# main_v2.net
KiCad netlist of a schematic drawn in EAGLE
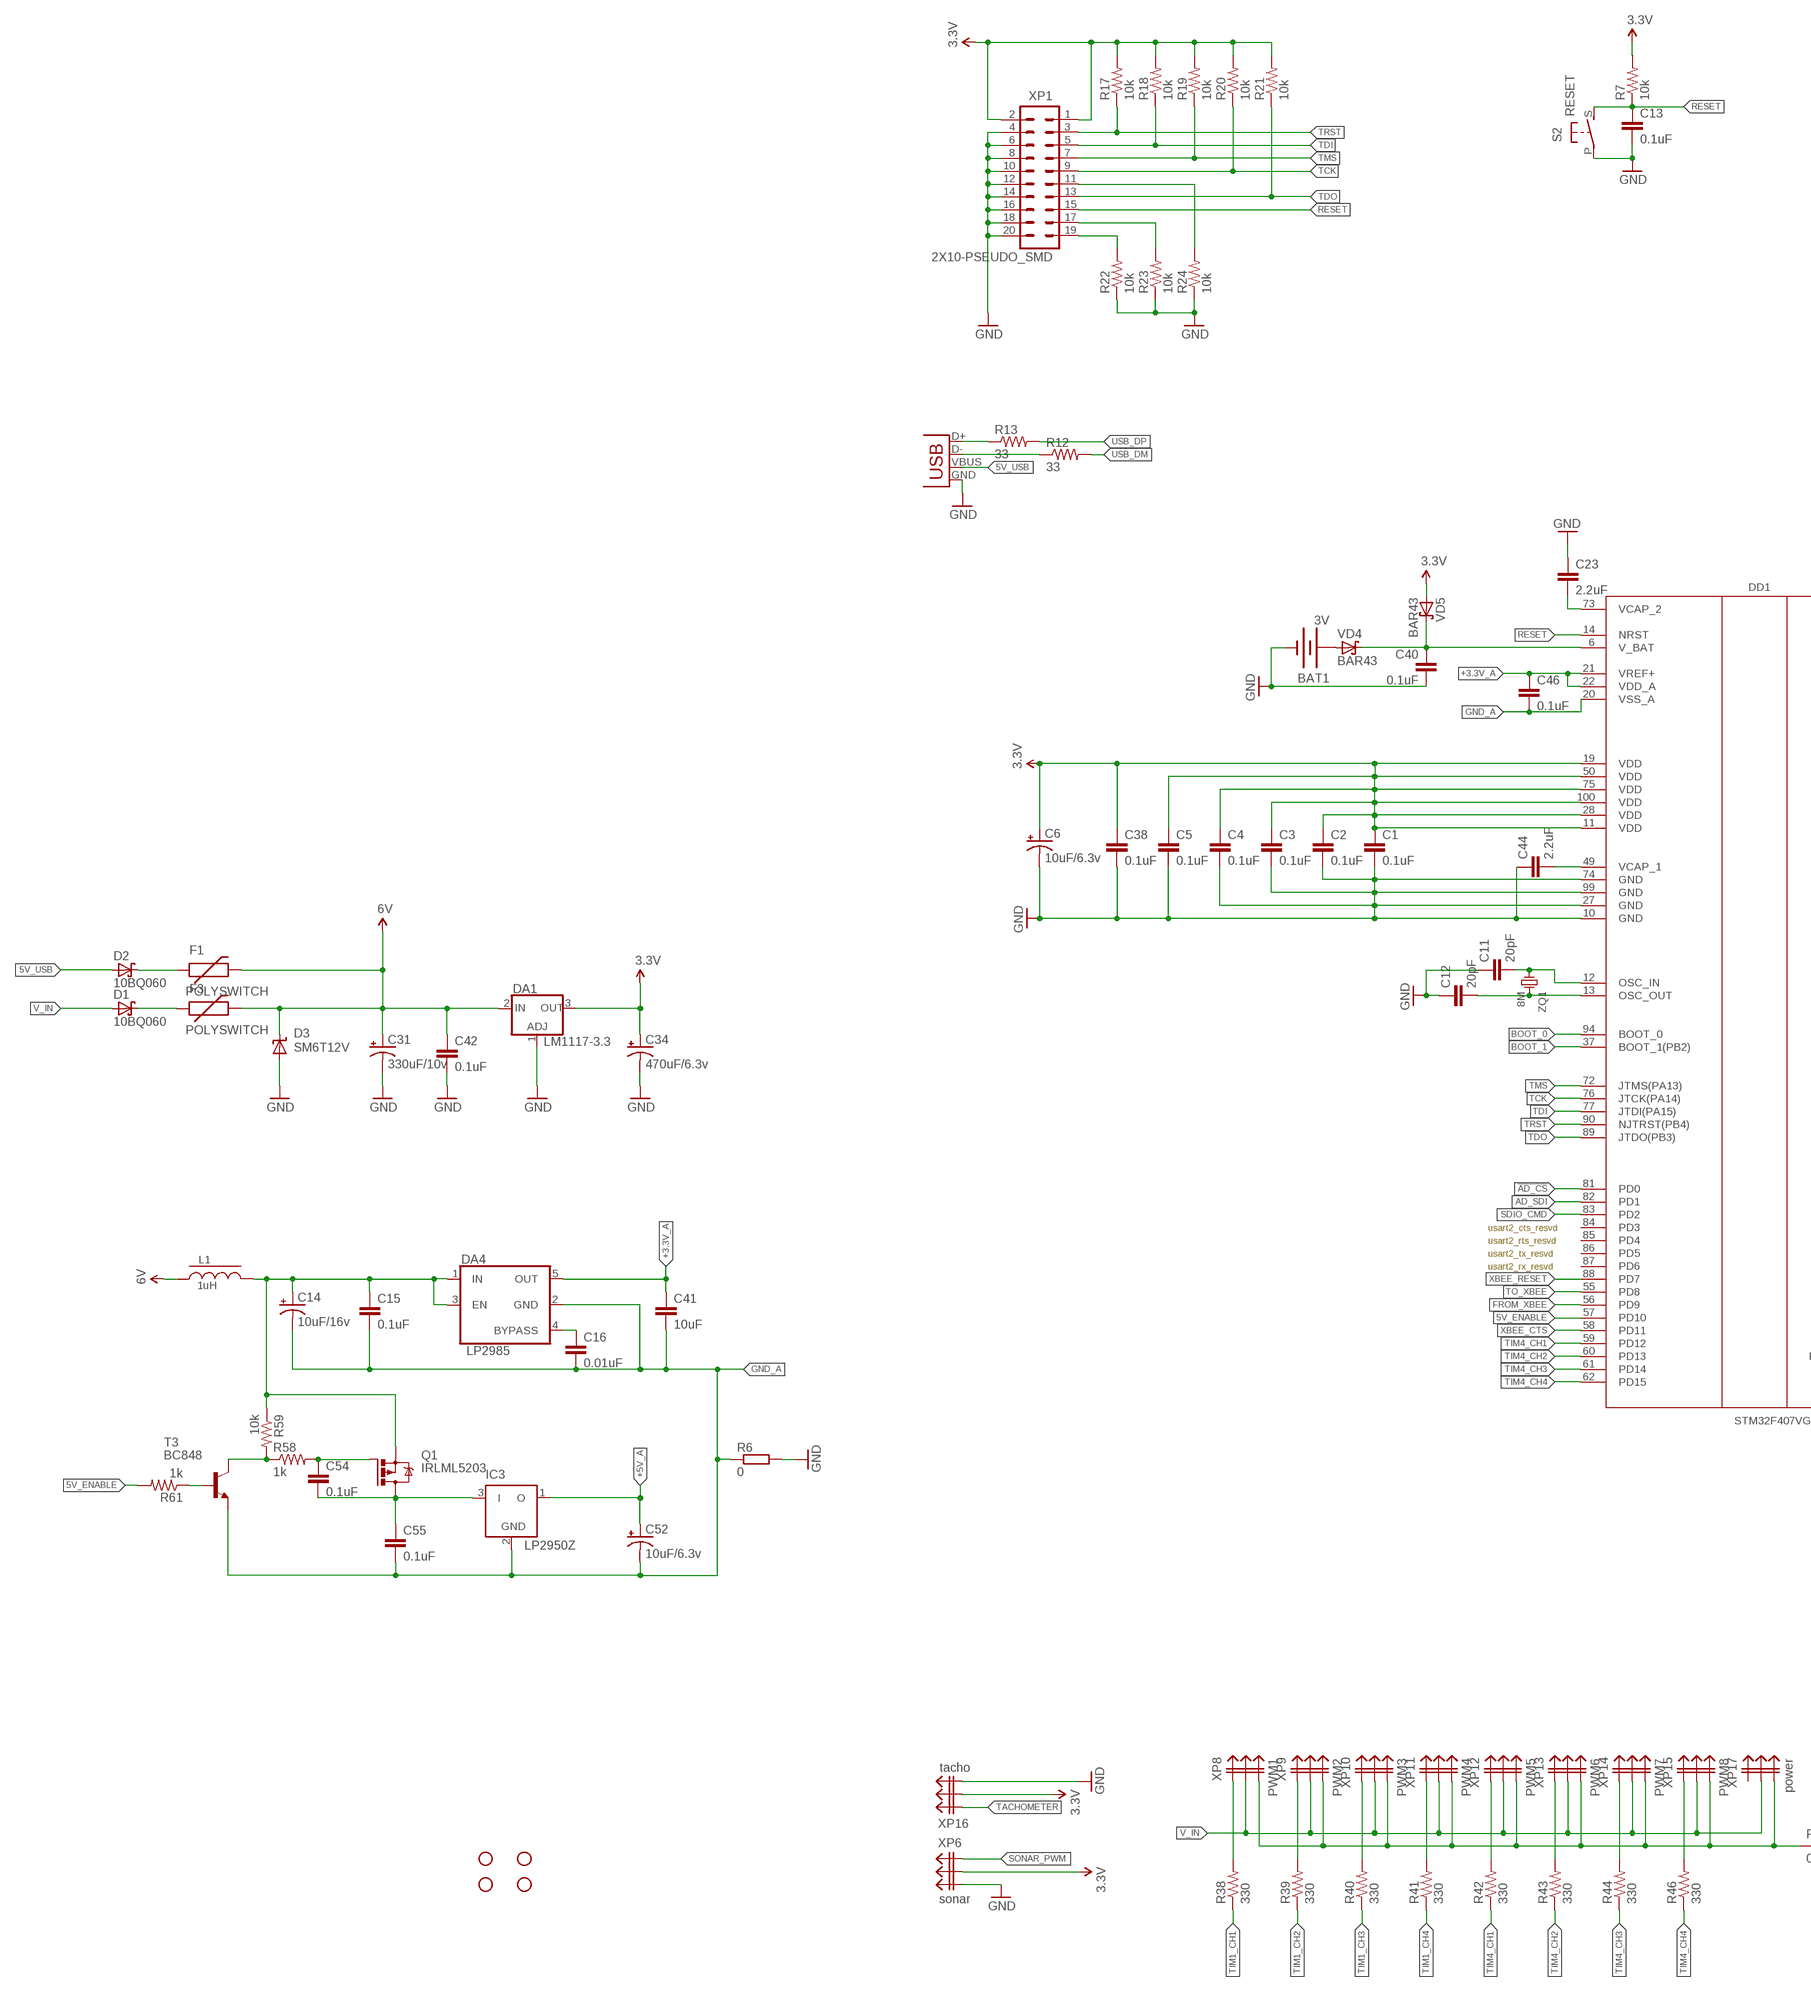
[diagram p0: schematic, sheet 1, part 1 of 3]
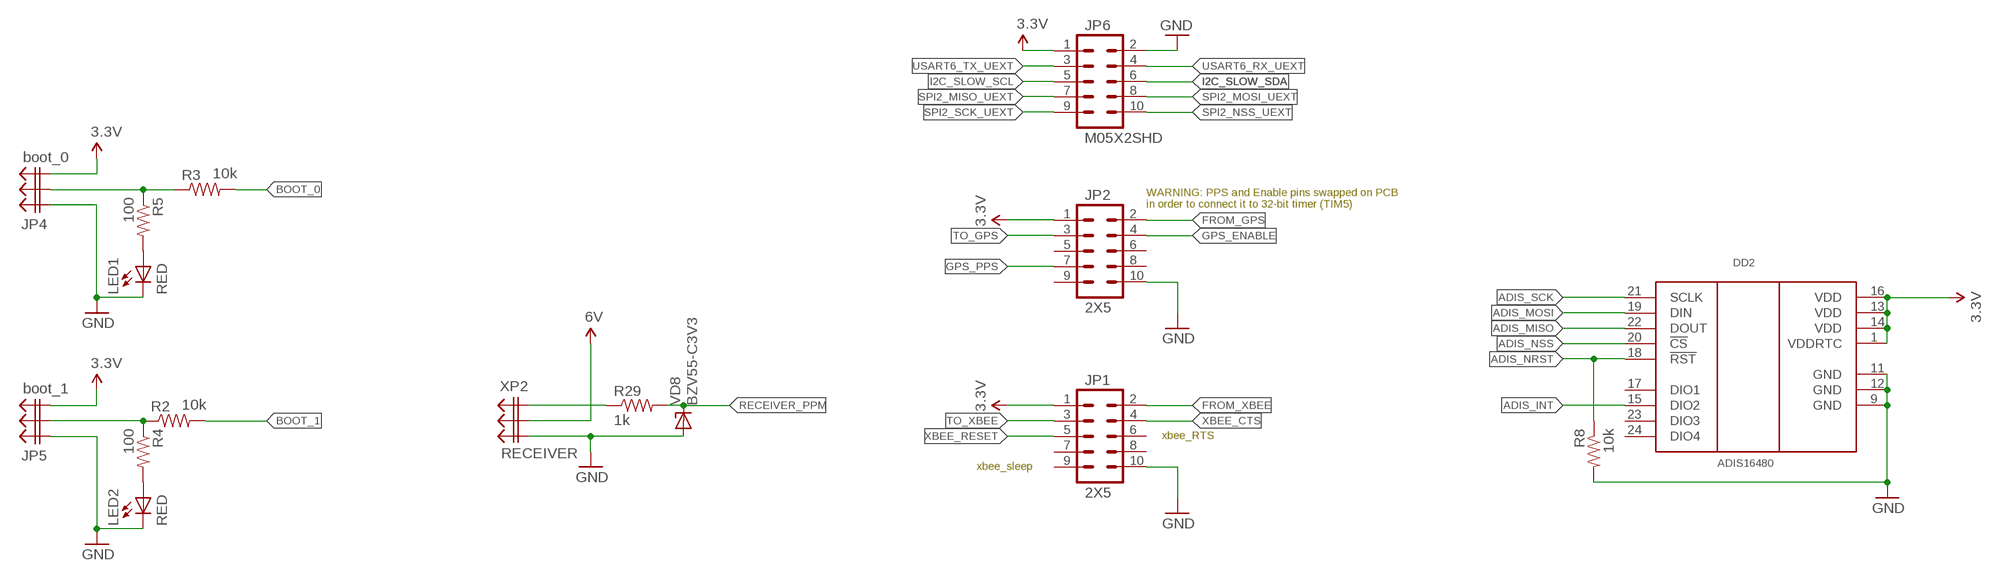
[diagram p1: schematic, sheet 1, part 2 of 3]
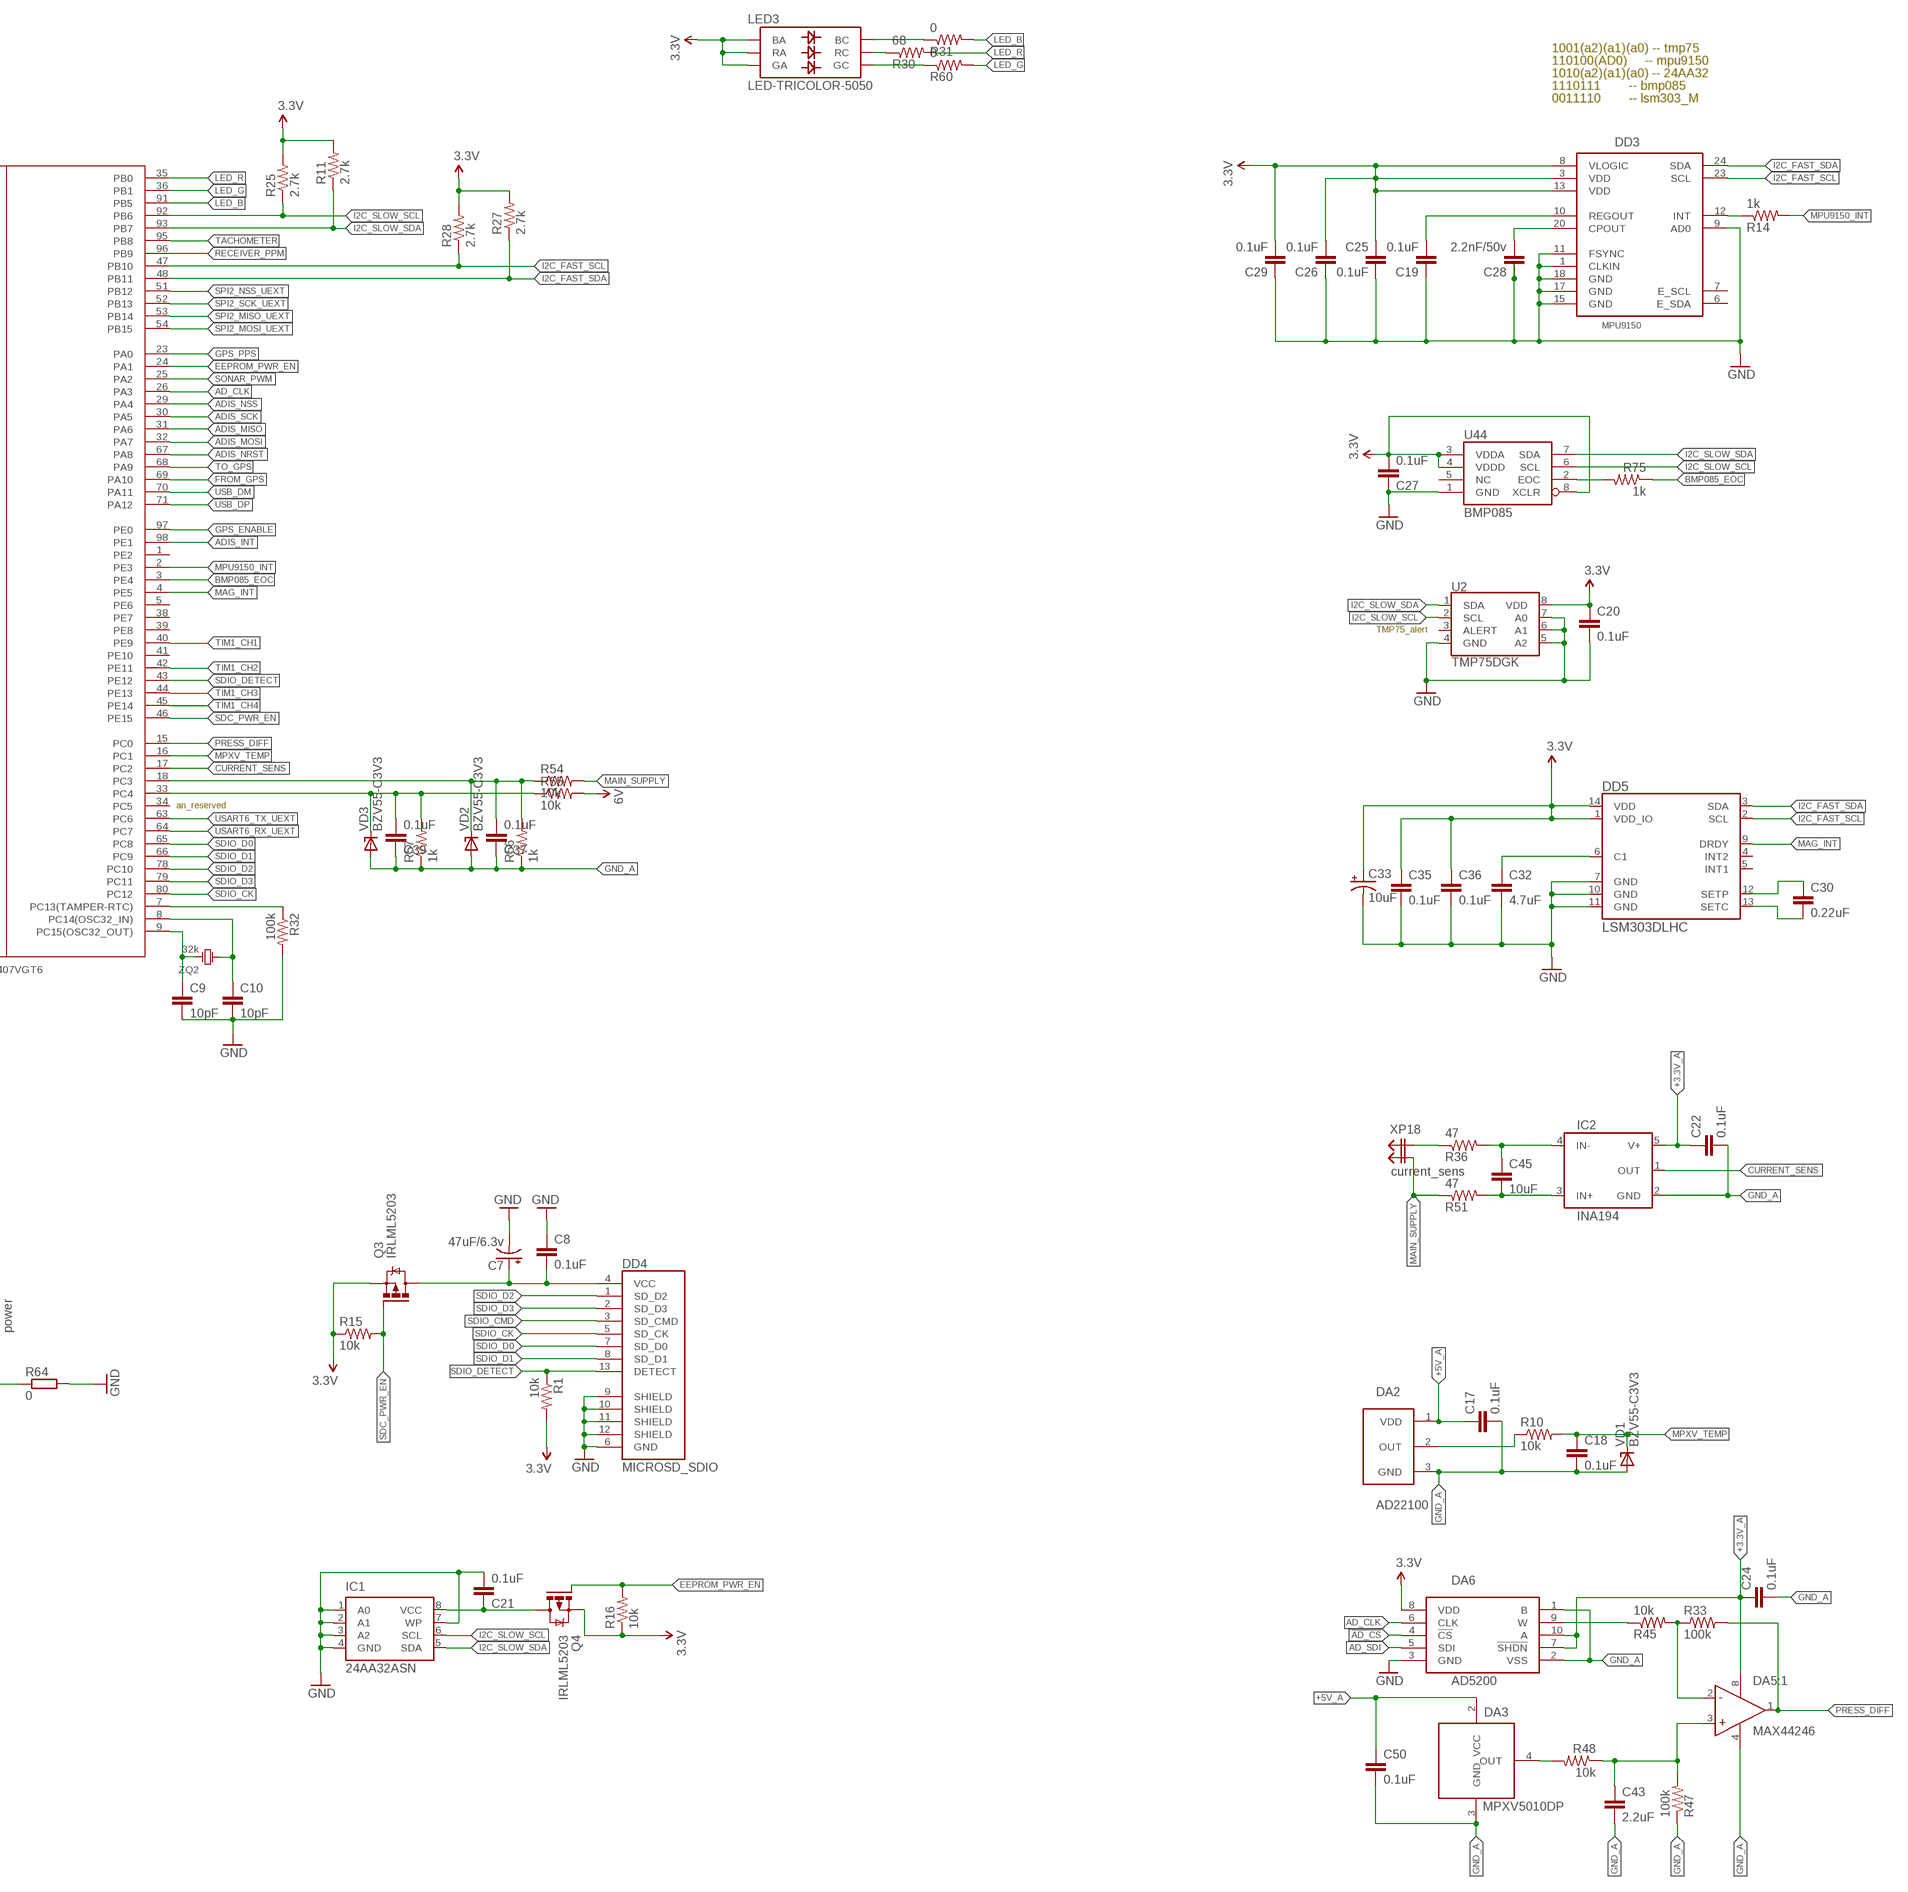
[diagram p2: schematic, sheet 1, part 3 of 3]

(export (version "E")
  (design (tool "Eeschema 10.0.6"))
  (components
    (comp (ref "BAT1")
      (value "3V")
      (footprint "eagle-import:BATTCOM_20MM_PTH")
      (libsource (lib "eagle-import") (part "BATTERY20PTH"))
    )
    (comp (ref "C1")
      (value "0.1uF")
      (footprint "eagle-import:0805")
      (libsource (lib "eagle-import") (part "CAP0805"))
    )
    (comp (ref "C2")
      (value "0.1uF")
      (footprint "eagle-import:0805")
      (libsource (lib "eagle-import") (part "CAP0805"))
    )
    (comp (ref "C3")
      (value "0.1uF")
      (footprint "eagle-import:0805")
      (libsource (lib "eagle-import") (part "CAP0805"))
    )
    (comp (ref "C4")
      (value "0.1uF")
      (footprint "eagle-import:0805")
      (libsource (lib "eagle-import") (part "CAP0805"))
    )
    (comp (ref "C5")
      (value "0.1uF")
      (footprint "eagle-import:0805")
      (libsource (lib "eagle-import") (part "CAP0805"))
    )
    (comp (ref "C6")
      (value "10uF/6.3v")
      (footprint "eagle-import:EIA3216-KIT")
      (libsource (lib "eagle-import") (part "CAP_POL1206-KIT"))
    )
    (comp (ref "C7")
      (value "47uF/6.3v")
      (footprint "eagle-import:EIA3216-KIT")
      (libsource (lib "eagle-import") (part "CAP_POL1206-KIT"))
    )
    (comp (ref "C8")
      (value "0.1uF")
      (footprint "eagle-import:0805")
      (libsource (lib "eagle-import") (part "CAP0805"))
    )
    (comp (ref "C9")
      (value "10pF")
      (footprint "eagle-import:0805")
      (libsource (lib "eagle-import") (part "CAP0805"))
    )
    (comp (ref "C10")
      (value "10pF")
      (footprint "eagle-import:0805")
      (libsource (lib "eagle-import") (part "CAP0805"))
    )
    (comp (ref "C11")
      (value "20pF")
      (footprint "eagle-import:0805")
      (libsource (lib "eagle-import") (part "CAP0805"))
    )
    (comp (ref "C12")
      (value "20pF")
      (footprint "eagle-import:0805")
      (libsource (lib "eagle-import") (part "CAP0805"))
    )
    (comp (ref "C13")
      (value "0.1uF")
      (footprint "eagle-import:0805")
      (libsource (lib "eagle-import") (part "CAP0805"))
    )
    (comp (ref "C14")
      (value "10uF/16v")
      (footprint "eagle-import:EIA3216-KIT")
      (libsource (lib "eagle-import") (part "CAP_POL1206-KIT"))
    )
    (comp (ref "C15")
      (value "0.1uF")
      (footprint "eagle-import:0805")
      (libsource (lib "eagle-import") (part "CAP0805"))
    )
    (comp (ref "C16")
      (value "0.01uF")
      (footprint "eagle-import:0805")
      (libsource (lib "eagle-import") (part "CAP0805"))
    )
    (comp (ref "C17")
      (value "0.1uF")
      (footprint "eagle-import:0805")
      (libsource (lib "eagle-import") (part "CAP0805"))
    )
    (comp (ref "C18")
      (value "0.1uF")
      (footprint "eagle-import:0805")
      (libsource (lib "eagle-import") (part "CAP0805"))
    )
    (comp (ref "C19")
      (value "0.1uF")
      (footprint "eagle-import:0805")
      (libsource (lib "eagle-import") (part "CAP0805"))
    )
    (comp (ref "C20")
      (value "0.1uF")
      (footprint "eagle-import:0805")
      (libsource (lib "eagle-import") (part "CAP0805"))
    )
    (comp (ref "C21")
      (value "0.1uF")
      (footprint "eagle-import:0805")
      (libsource (lib "eagle-import") (part "CAP0805"))
    )
    (comp (ref "C22")
      (value "0.1uF")
      (footprint "eagle-import:0805")
      (libsource (lib "eagle-import") (part "CAP0805"))
    )
    (comp (ref "C23")
      (value "2.2uF")
      (footprint "eagle-import:0805")
      (libsource (lib "eagle-import") (part "CAP0805"))
    )
    (comp (ref "C24")
      (value "0.1uF")
      (footprint "eagle-import:0805")
      (libsource (lib "eagle-import") (part "CAP0805"))
    )
    (comp (ref "C25")
      (value "0.1uF")
      (footprint "eagle-import:0805")
      (libsource (lib "eagle-import") (part "CAP0805"))
    )
    (comp (ref "C26")
      (value "0.1uF")
      (footprint "eagle-import:0805")
      (libsource (lib "eagle-import") (part "CAP0805"))
    )
    (comp (ref "C27")
      (value "0.1uF")
      (footprint "eagle-import:0805")
      (libsource (lib "eagle-import") (part "CAP0805"))
    )
    (comp (ref "C28")
      (value "2.2nF/50v")
      (footprint "eagle-import:0805")
      (libsource (lib "eagle-import") (part "CAP0805"))
    )
    (comp (ref "C29")
      (value "0.1uF")
      (footprint "eagle-import:0805")
      (libsource (lib "eagle-import") (part "CAP0805"))
    )
    (comp (ref "C30")
      (value "0.22uF")
      (footprint "eagle-import:0805")
      (libsource (lib "eagle-import") (part "CAP0805"))
    )
    (comp (ref "C31")
      (value "330uF/10v")
      (footprint "eagle-import:EIA7343")
      (libsource (lib "eagle-import") (part "barthess_CAP_POL7343"))
    )
    (comp (ref "C32")
      (value "4.7uF")
      (footprint "eagle-import:0805")
      (libsource (lib "eagle-import") (part "CAP0805"))
    )
    (comp (ref "C33")
      (value "10uF")
      (footprint "eagle-import:EIA3216-KIT")
      (libsource (lib "eagle-import") (part "CAP_POL1206-KIT"))
    )
    (comp (ref "C34")
      (value "470uF/6.3v")
      (footprint "eagle-import:EIA7343")
      (libsource (lib "eagle-import") (part "barthess_CAP_POL7343"))
    )
    (comp (ref "C35")
      (value "0.1uF")
      (footprint "eagle-import:0805")
      (libsource (lib "eagle-import") (part "CAP0805"))
    )
    (comp (ref "C36")
      (value "0.1uF")
      (footprint "eagle-import:0805")
      (libsource (lib "eagle-import") (part "CAP0805"))
    )
    (comp (ref "C37")
      (value "0.1uF")
      (footprint "eagle-import:0805")
      (libsource (lib "eagle-import") (part "CAP0805"))
    )
    (comp (ref "C38")
      (value "0.1uF")
      (footprint "eagle-import:0805")
      (libsource (lib "eagle-import") (part "CAP0805"))
    )
    (comp (ref "C39")
      (value "0.1uF")
      (footprint "eagle-import:0805")
      (libsource (lib "eagle-import") (part "CAP0805"))
    )
    (comp (ref "C40")
      (value "0.1uF")
      (footprint "eagle-import:0805")
      (libsource (lib "eagle-import") (part "CAP0805"))
    )
    (comp (ref "C41")
      (value "10uF")
      (footprint "eagle-import:1206")
      (libsource (lib "eagle-import") (part "CAP1206"))
    )
    (comp (ref "C42")
      (value "0.1uF")
      (footprint "eagle-import:0805")
      (libsource (lib "eagle-import") (part "CAP0805"))
    )
    (comp (ref "C43")
      (value "2.2uF")
      (footprint "eagle-import:0805")
      (libsource (lib "eagle-import") (part "CAP0805"))
    )
    (comp (ref "C44")
      (value "2.2uF")
      (footprint "eagle-import:0805")
      (libsource (lib "eagle-import") (part "CAP0805"))
    )
    (comp (ref "C45")
      (value "10uF")
      (footprint "eagle-import:1206")
      (libsource (lib "eagle-import") (part "CAP1206"))
    )
    (comp (ref "C46")
      (value "0.1uF")
      (footprint "eagle-import:0805")
      (libsource (lib "eagle-import") (part "CAP0805"))
    )
    (comp (ref "C50")
      (value "0.1uF")
      (footprint "eagle-import:0805")
      (libsource (lib "eagle-import") (part "CAP0805"))
    )
    (comp (ref "C52")
      (value "10uF/6.3v")
      (footprint "eagle-import:EIA3216-KIT")
      (libsource (lib "eagle-import") (part "CAP_POL1206-KIT"))
    )
    (comp (ref "C54")
      (value "0.1uF")
      (footprint "eagle-import:0805")
      (libsource (lib "eagle-import") (part "CAP0805"))
    )
    (comp (ref "C55")
      (value "0.1uF")
      (footprint "eagle-import:0805")
      (libsource (lib "eagle-import") (part "CAP0805"))
    )
    (comp (ref "D1")
      (value "10BQ060")
      (footprint "eagle-import:SMB")
      (libsource (lib "eagle-import") (part "SCHOTTKY-DIODESMD"))
    )
    (comp (ref "D2")
      (value "10BQ060")
      (footprint "eagle-import:SMB")
      (libsource (lib "eagle-import") (part "SCHOTTKY-DIODESMD"))
    )
    (comp (ref "D3")
      (value "SM6T12V")
      (footprint "eagle-import:SMBJ")
      (libsource (lib "eagle-import") (part "SUPPRESSOR-SMBJ"))
    )
    (comp (ref "DA1")
      (value "LM1117-3.3")
      (footprint "eagle-import:TO252")
      (libsource (lib "eagle-import") (part "LM1117DTX"))
    )
    (comp (ref "DA2")
      (value "AD22100")
      (footprint "eagle-import:TO92")
      (libsource (lib "eagle-import") (part "AD22100"))
    )
    (comp (ref "DA3")
      (value "MPXV5010DP")
      (footprint "eagle-import:482")
      (libsource (lib "eagle-import") (part "MPXV5010DP"))
    )
    (comp (ref "DA4")
      (value "LP2985")
      (footprint "eagle-import:SOT23-5")
      (libsource (lib "eagle-import") (part "LP2985"))
    )
    (comp (ref "DA5")
      (value "MAX44246")
      (footprint "eagle-import:MSOP8")
      (libsource (lib "eagle-import") (part "MAX44246"))
    )
    (comp (ref "DA6")
      (value "AD5200")
      (footprint "eagle-import:MSOP10")
      (libsource (lib "eagle-import") (part "AD5200"))
    )
    (comp (ref "DD1")
      (value "STM32F407VGT6")
      (footprint "eagle-import:TQFP100")
      (libsource (lib "eagle-import") (part "STM32F407VGT6"))
    )
    (comp (ref "DD2")
      (value "ADIS16480")
      (footprint "eagle-import:ADIS16480")
      (libsource (lib "eagle-import") (part "ADIS16480"))
    )
    (comp (ref "DD3")
      (value "MPU9150")
      (footprint "eagle-import:QFN-24-NP")
      (libsource (lib "eagle-import") (part "MPU-9150QFN-24-NP"))
    )
    (comp (ref "DD4")
      (value "MICROSD_SDIO")
      (footprint "eagle-import:MICROSD")
      (libsource (lib "eagle-import") (part "MICROSD_SDIO"))
    )
    (comp (ref "DD5")
      (value "LSM303DLHC")
      (footprint "eagle-import:LGA14")
      (libsource (lib "eagle-import") (part "LSM303DLHC"))
    )
    (comp (ref "F1")
      (value "POLYSWITCH")
      (footprint "eagle-import:1812")
      (libsource (lib "eagle-import") (part "POLYSWITCH"))
    )
    (comp (ref "F3")
      (value "POLYSWITCH")
      (footprint "eagle-import:1812")
      (libsource (lib "eagle-import") (part "POLYSWITCH"))
    )
    (comp (ref "IC1")
      (value "24AA32ASN")
      (footprint "eagle-import:SO-08")
      (fields (field (name "MF") "MICROCHIP") (field (name "MPN") "24AA32A-I/SN"))
      (libsource (lib "eagle-import") (part "24SNAA32A"))
    )
    (comp (ref "IC2")
      (value "INA194")
      (footprint "eagle-import:SOT23-5")
      (fields (field (name "MF") "TEXAS INSTRUMENTS") (field (name "MPN") "INA168NA/250"))
      (libsource (lib "eagle-import") (part "INA194"))
    )
    (comp (ref "IC3")
      (value "LP2950Z")
      (footprint "eagle-import:TO92")
      (libsource (lib "eagle-import") (part "LP2950Z"))
    )
    (comp (ref "JP1")
      (value "2X5")
      (footprint "eagle-import:PLD_2X05_PSEUDOSMD")
      (libsource (lib "eagle-import") (part "2X5"))
    )
    (comp (ref "JP2")
      (value "2X5")
      (footprint "eagle-import:PLD_2X05_PSEUDOSMD")
      (libsource (lib "eagle-import") (part "2X5"))
    )
    (comp (ref "JP3")
      (value "STAND-OFF")
      (footprint "eagle-import:STAND-OFF")
      (libsource (lib "eagle-import") (part "STAND-OFF"))
    )
    (comp (ref "JP4")
      (value "boot_0")
      (footprint "eagle-import:PLD_1X03")
      (libsource (lib "eagle-import") (part "PLD_1X03"))
    )
    (comp (ref "JP5")
      (value "boot_1")
      (footprint "eagle-import:PLD_1X03")
      (libsource (lib "eagle-import") (part "PLD_1X03"))
    )
    (comp (ref "JP6")
      (value "M05X2SHD")
      (footprint "eagle-import:2X5-SHROUDED")
      (libsource (lib "eagle-import") (part "M05X2SHD"))
    )
    (comp (ref "JP7")
      (value "STAND-OFF")
      (footprint "eagle-import:STAND-OFF")
      (libsource (lib "eagle-import") (part "STAND-OFF"))
    )
    (comp (ref "JP8")
      (value "STAND-OFF")
      (footprint "eagle-import:STAND-OFF")
      (libsource (lib "eagle-import") (part "STAND-OFF"))
    )
    (comp (ref "JP9")
      (value "STAND-OFF")
      (footprint "eagle-import:STAND-OFF")
      (libsource (lib "eagle-import") (part "STAND-OFF"))
    )
    (comp (ref "L1")
      (value "1uH")
      (footprint "eagle-import:L0603")
      (libsource (lib "eagle-import") (part "EXC3BP"))
    )
    (comp (ref "LED1")
      (value "RED")
      (footprint "eagle-import:LED-0805")
      (libsource (lib "eagle-import") (part "LED0805"))
    )
    (comp (ref "LED2")
      (value "RED")
      (footprint "eagle-import:LED-0805")
      (libsource (lib "eagle-import") (part "LED0805"))
    )
    (comp (ref "LED3")
      (value "LED-TRICOLOR-5050")
      (footprint "eagle-import:LED-TRICOLOR-5050")
      (libsource (lib "eagle-import") (part "LED-TRICOLOR-5050"))
    )
    (comp (ref "Q1")
      (value "IRLML5203")
      (footprint "eagle-import:MICRO3")
      (libsource (lib "eagle-import") (part "IRLML5203"))
    )
    (comp (ref "Q3")
      (value "IRLML5203")
      (footprint "eagle-import:MICRO3")
      (libsource (lib "eagle-import") (part "IRLML5203"))
    )
    (comp (ref "Q4")
      (value "IRLML5203")
      (footprint "eagle-import:MICRO3")
      (libsource (lib "eagle-import") (part "IRLML5203"))
    )
    (comp (ref "R1")
      (value "10k")
      (footprint "eagle-import:0805")
      (libsource (lib "eagle-import") (part "RESISTOR0805-RES"))
    )
    (comp (ref "R2")
      (value "10k")
      (footprint "eagle-import:0805")
      (libsource (lib "eagle-import") (part "RESISTOR0805-RES"))
    )
    (comp (ref "R3")
      (value "10k")
      (footprint "eagle-import:0805")
      (libsource (lib "eagle-import") (part "RESISTOR0805-RES"))
    )
    (comp (ref "R4")
      (value "100")
      (footprint "eagle-import:0805")
      (libsource (lib "eagle-import") (part "RESISTOR0805-RES"))
    )
    (comp (ref "R5")
      (value "100")
      (footprint "eagle-import:0805")
      (libsource (lib "eagle-import") (part "RESISTOR0805-RES"))
    )
    (comp (ref "R6")
      (value "0")
      (footprint "eagle-import:1206")
      (libsource (lib "eagle-import") (part "barthess_RESISTOR1206"))
    )
    (comp (ref "R7")
      (value "10k")
      (footprint "eagle-import:0805")
      (libsource (lib "eagle-import") (part "RESISTOR0805-RES"))
    )
    (comp (ref "R8")
      (value "10k")
      (footprint "eagle-import:0805")
      (libsource (lib "eagle-import") (part "RESISTOR0805-RES"))
    )
    (comp (ref "R10")
      (value "10k")
      (footprint "eagle-import:0805")
      (libsource (lib "eagle-import") (part "RESISTOR0805-RES"))
    )
    (comp (ref "R11")
      (value "2.7k")
      (footprint "eagle-import:0805")
      (libsource (lib "eagle-import") (part "RESISTOR0805-RES"))
    )
    (comp (ref "R12")
      (value "33")
      (footprint "eagle-import:0805")
      (libsource (lib "eagle-import") (part "RESISTOR0805-RES"))
    )
    (comp (ref "R13")
      (value "33")
      (footprint "eagle-import:0805")
      (libsource (lib "eagle-import") (part "RESISTOR0805-RES"))
    )
    (comp (ref "R14")
      (value "1k")
      (footprint "eagle-import:0805")
      (libsource (lib "eagle-import") (part "RESISTOR0805-RES"))
    )
    (comp (ref "R15")
      (value "10k")
      (footprint "eagle-import:0805")
      (libsource (lib "eagle-import") (part "RESISTOR0805-RES"))
    )
    (comp (ref "R16")
      (value "10k")
      (footprint "eagle-import:0805")
      (libsource (lib "eagle-import") (part "RESISTOR0805-RES"))
    )
    (comp (ref "R17")
      (value "10k")
      (footprint "eagle-import:0805")
      (libsource (lib "eagle-import") (part "RESISTOR0805-RES"))
    )
    (comp (ref "R18")
      (value "10k")
      (footprint "eagle-import:0805")
      (libsource (lib "eagle-import") (part "RESISTOR0805-RES"))
    )
    (comp (ref "R19")
      (value "10k")
      (footprint "eagle-import:0805")
      (libsource (lib "eagle-import") (part "RESISTOR0805-RES"))
    )
    (comp (ref "R20")
      (value "10k")
      (footprint "eagle-import:0805")
      (libsource (lib "eagle-import") (part "RESISTOR0805-RES"))
    )
    (comp (ref "R21")
      (value "10k")
      (footprint "eagle-import:0805")
      (libsource (lib "eagle-import") (part "RESISTOR0805-RES"))
    )
    (comp (ref "R22")
      (value "10k")
      (footprint "eagle-import:0805")
      (libsource (lib "eagle-import") (part "RESISTOR0805-RES"))
    )
    (comp (ref "R23")
      (value "10k")
      (footprint "eagle-import:0805")
      (libsource (lib "eagle-import") (part "RESISTOR0805-RES"))
    )
    (comp (ref "R24")
      (value "10k")
      (footprint "eagle-import:0805")
      (libsource (lib "eagle-import") (part "RESISTOR0805-RES"))
    )
    (comp (ref "R25")
      (value "2.7k")
      (footprint "eagle-import:0805")
      (libsource (lib "eagle-import") (part "RESISTOR0805-RES"))
    )
    (comp (ref "R27")
      (value "2.7k")
      (footprint "eagle-import:0805")
      (libsource (lib "eagle-import") (part "RESISTOR0805-RES"))
    )
    (comp (ref "R28")
      (value "2.7k")
      (footprint "eagle-import:0805")
      (libsource (lib "eagle-import") (part "RESISTOR0805-RES"))
    )
    (comp (ref "R29")
      (value "1k")
      (footprint "eagle-import:0805")
      (libsource (lib "eagle-import") (part "RESISTOR0805-RES"))
    )
    (comp (ref "R30")
      (value "68")
      (footprint "eagle-import:0805")
      (libsource (lib "eagle-import") (part "RESISTOR0805-RES"))
    )
    (comp (ref "R31")
      (value "0")
      (footprint "eagle-import:0805")
      (libsource (lib "eagle-import") (part "RESISTOR0805-RES"))
    )
    (comp (ref "R32")
      (value "100k")
      (footprint "eagle-import:0805")
      (libsource (lib "eagle-import") (part "RESISTOR0805-RES"))
    )
    (comp (ref "R33")
      (value "100k")
      (footprint "eagle-import:0805")
      (libsource (lib "eagle-import") (part "RESISTOR0805-RES"))
    )
    (comp (ref "R36")
      (value "47")
      (footprint "eagle-import:0805")
      (libsource (lib "eagle-import") (part "RESISTOR0805-RES"))
    )
    (comp (ref "R38")
      (value "330")
      (footprint "eagle-import:0805")
      (libsource (lib "eagle-import") (part "RESISTOR0805-RES"))
    )
    (comp (ref "R39")
      (value "330")
      (footprint "eagle-import:0805")
      (libsource (lib "eagle-import") (part "RESISTOR0805-RES"))
    )
    (comp (ref "R40")
      (value "330")
      (footprint "eagle-import:0805")
      (libsource (lib "eagle-import") (part "RESISTOR0805-RES"))
    )
    (comp (ref "R41")
      (value "330")
      (footprint "eagle-import:0805")
      (libsource (lib "eagle-import") (part "RESISTOR0805-RES"))
    )
    (comp (ref "R42")
      (value "330")
      (footprint "eagle-import:0805")
      (libsource (lib "eagle-import") (part "RESISTOR0805-RES"))
    )
    (comp (ref "R43")
      (value "330")
      (footprint "eagle-import:0805")
      (libsource (lib "eagle-import") (part "RESISTOR0805-RES"))
    )
    (comp (ref "R44")
      (value "330")
      (footprint "eagle-import:0805")
      (libsource (lib "eagle-import") (part "RESISTOR0805-RES"))
    )
    (comp (ref "R45")
      (value "10k")
      (footprint "eagle-import:0805")
      (libsource (lib "eagle-import") (part "RESISTOR0805-RES"))
    )
    (comp (ref "R46")
      (value "330")
      (footprint "eagle-import:0805")
      (libsource (lib "eagle-import") (part "RESISTOR0805-RES"))
    )
    (comp (ref "R47")
      (value "100k")
      (footprint "eagle-import:0805")
      (libsource (lib "eagle-import") (part "RESISTOR0805-RES"))
    )
    (comp (ref "R48")
      (value "10k")
      (footprint "eagle-import:0805")
      (libsource (lib "eagle-import") (part "RESISTOR0805-RES"))
    )
    (comp (ref "R51")
      (value "47")
      (footprint "eagle-import:0805")
      (libsource (lib "eagle-import") (part "RESISTOR0805-RES"))
    )
    (comp (ref "R54")
      (value "10k")
      (footprint "eagle-import:0805")
      (libsource (lib "eagle-import") (part "RESISTOR0805-RES"))
    )
    (comp (ref "R55")
      (value "10k")
      (footprint "eagle-import:0805")
      (libsource (lib "eagle-import") (part "RESISTOR0805-RES"))
    )
    (comp (ref "R56")
      (value "1k")
      (footprint "eagle-import:0805")
      (libsource (lib "eagle-import") (part "RESISTOR0805-RES"))
    )
    (comp (ref "R57")
      (value "1k")
      (footprint "eagle-import:0805")
      (libsource (lib "eagle-import") (part "RESISTOR0805-RES"))
    )
    (comp (ref "R58")
      (value "1k")
      (footprint "eagle-import:0805")
      (libsource (lib "eagle-import") (part "RESISTOR0805-RES"))
    )
    (comp (ref "R59")
      (value "10k")
      (footprint "eagle-import:0805")
      (libsource (lib "eagle-import") (part "RESISTOR0805-RES"))
    )
    (comp (ref "R60")
      (value "0")
      (footprint "eagle-import:0805")
      (libsource (lib "eagle-import") (part "RESISTOR0805-RES"))
    )
    (comp (ref "R61")
      (value "1k")
      (footprint "eagle-import:0805")
      (libsource (lib "eagle-import") (part "RESISTOR0805-RES"))
    )
    (comp (ref "R64")
      (value "0")
      (footprint "eagle-import:1206")
      (libsource (lib "eagle-import") (part "barthess_RESISTOR1206"))
    )
    (comp (ref "R75")
      (value "1k")
      (footprint "eagle-import:0805")
      (libsource (lib "eagle-import") (part "RESISTOR0805-RES"))
    )
    (comp (ref "S2")
      (value "RESET")
      (footprint "eagle-import:BUTTON_6X3.5")
      (libsource (lib "eagle-import") (part "BUTTON_6X3.5"))
    )
    (comp (ref "T3")
      (value "BC848")
      (footprint "eagle-import:SOT23")
      (libsource (lib "eagle-import") (part "BC848"))
    )
    (comp (ref "U2")
      (value "TMP75DGK")
      (footprint "eagle-import:MSOP8")
      (libsource (lib "eagle-import") (part "TMP75DGK"))
    )
    (comp (ref "U44")
      (value "BMP085")
      (footprint "eagle-import:BMP085")
      (libsource (lib "eagle-import") (part "BMP085"))
    )
    (comp (ref "VD1")
      (value "BZV55-C3V3")
      (footprint "eagle-import:SOD80C")
      (fields (field (name "PARTNO") "?"))
      (libsource (lib "eagle-import") (part "BZV55-C3V3"))
    )
    (comp (ref "VD2")
      (value "BZV55-C3V3")
      (footprint "eagle-import:SOD80C")
      (fields (field (name "PARTNO") "?"))
      (libsource (lib "eagle-import") (part "BZV55-C3V3"))
    )
    (comp (ref "VD3")
      (value "BZV55-C3V3")
      (footprint "eagle-import:SOD80C")
      (fields (field (name "PARTNO") "?"))
      (libsource (lib "eagle-import") (part "BZV55-C3V3"))
    )
    (comp (ref "VD4")
      (value "BAR43")
      (footprint "eagle-import:SOT23-3")
      (libsource (lib "eagle-import") (part "BAR43"))
    )
    (comp (ref "VD5")
      (value "BAR43")
      (footprint "eagle-import:SOT23-3")
      (libsource (lib "eagle-import") (part "BAR43"))
    )
    (comp (ref "VD8")
      (value "BZV55-C3V3")
      (footprint "eagle-import:SOD80C")
      (fields (field (name "PARTNO") "?"))
      (libsource (lib "eagle-import") (part "BZV55-C3V3"))
    )
    (comp (ref "X1")
      (value "USB-SMD-NS")
      (footprint "eagle-import:USB-MINIB-NOSTOP")
      (libsource (lib "eagle-import") (part "USB-SMD-NS"))
    )
    (comp (ref "XP1")
      (value "2X10-PSEUDO_SMD")
      (footprint "eagle-import:PLD_2X10_PSEUDOSMD")
      (libsource (lib "eagle-import") (part "2X10-PSEUDO_SMD"))
    )
    (comp (ref "XP2")
      (value "RECEIVER")
      (footprint "eagle-import:PLD_1X03")
      (libsource (lib "eagle-import") (part "PLD_1X03"))
    )
    (comp (ref "XP6")
      (value "sonar")
      (footprint "eagle-import:PLD_1X03")
      (libsource (lib "eagle-import") (part "PLD_1X03"))
    )
    (comp (ref "XP8")
      (value "PWM1")
      (footprint "eagle-import:PLD_1X03")
      (libsource (lib "eagle-import") (part "PLD_1X03"))
    )
    (comp (ref "XP9")
      (value "PWM2")
      (footprint "eagle-import:PLD_1X03")
      (libsource (lib "eagle-import") (part "PLD_1X03"))
    )
    (comp (ref "XP10")
      (value "PWM3")
      (footprint "eagle-import:PLD_1X03")
      (libsource (lib "eagle-import") (part "PLD_1X03"))
    )
    (comp (ref "XP11")
      (value "PWM4")
      (footprint "eagle-import:PLD_1X03")
      (libsource (lib "eagle-import") (part "PLD_1X03"))
    )
    (comp (ref "XP12")
      (value "PWM5")
      (footprint "eagle-import:PLD_1X03")
      (libsource (lib "eagle-import") (part "PLD_1X03"))
    )
    (comp (ref "XP13")
      (value "PWM6")
      (footprint "eagle-import:PLD_1X03")
      (libsource (lib "eagle-import") (part "PLD_1X03"))
    )
    (comp (ref "XP14")
      (value "PWM7")
      (footprint "eagle-import:PLD_1X03")
      (libsource (lib "eagle-import") (part "PLD_1X03"))
    )
    (comp (ref "XP15")
      (value "PWM8")
      (footprint "eagle-import:PLD_1X03")
      (libsource (lib "eagle-import") (part "PLD_1X03"))
    )
    (comp (ref "XP16")
      (value "tacho")
      (footprint "eagle-import:PLD_1X03")
      (libsource (lib "eagle-import") (part "PLD_1X03"))
    )
    (comp (ref "XP17")
      (value "power")
      (footprint "eagle-import:PLD_1X03")
      (libsource (lib "eagle-import") (part "PLD_1X03"))
    )
    (comp (ref "XP18")
      (value "current_sens")
      (footprint "eagle-import:PLD_1X02")
      (libsource (lib "eagle-import") (part "1X2DIP"))
    )
    (comp (ref "ZQ1")
      (value "8M")
      (footprint "eagle-import:CRYSTAL-SMD-5X3")
      (libsource (lib "eagle-import") (part "CRYSTAL5X3"))
    )
    (comp (ref "ZQ2")
      (value "32k")
      (footprint "eagle-import:CRYSTAL-32KHZ-SMD-3.2X1.5")
      (libsource (lib "eagle-import") (part "CRYSTAL3.2X.1.5"))
    )
  )
  (nets
    (net (code "1") (name "+3.3V_A") (class "Default")
      (node (ref "C22") (pin "1") (pinfunction "1_1") (pintype "passive"))
      (node (ref "C24") (pin "1") (pinfunction "1_1") (pintype "passive"))
      (node (ref "C41") (pin "1") (pinfunction "1_1") (pintype "passive"))
      (node (ref "C46") (pin "1") (pinfunction "1_1") (pintype "passive"))
      (node (ref "DA4") (pin "5") (pinfunction "OUT_5") (pintype "power_in"))
      (node (ref "DA5") (pin "8") (pinfunction "+V_8") (pintype "power_in"))
      (node (ref "DA6") (pin "10") (pinfunction "A_10") (pintype "bidirectional"))
      (node (ref "DA6") (pin "7") (pinfunction "~{SHDN}_7") (pintype "bidirectional"))
      (node (ref "DD1") (pin "21") (pinfunction "VREF+_21") (pintype "power_in"))
      (node (ref "DD1") (pin "22") (pinfunction "VDD_A_22") (pintype "power_in"))
      (node (ref "IC2") (pin "5") (pinfunction "V+_5") (pintype "power_in"))
    )
    (net (code "2") (name "+5V_A") (class "Default")
      (node (ref "C17") (pin "1") (pinfunction "1_1") (pintype "passive"))
      (node (ref "C50") (pin "1") (pinfunction "1_1") (pintype "passive"))
      (node (ref "C52") (pin "A") (pinfunction "+_A") (pintype "passive"))
      (node (ref "DA2") (pin "1") (pinfunction "VDD_1") (pintype "power_in"))
      (node (ref "DA3") (pin "2") (pinfunction "VCC_2") (pintype "power_in"))
      (node (ref "IC3") (pin "1") (pinfunction "O_1") (pintype "input"))
    )
    (net (code "3") (name "/~{AD_CS}") (class "Default")
      (node (ref "DA6") (pin "4") (pinfunction "~{CS}_4") (pintype "bidirectional"))
      (node (ref "DD1") (pin "81") (pinfunction "PD0_81") (pintype "bidirectional"))
    )
    (net (code "4") (name "3.3V") (class "Default")
      (node (ref "C1") (pin "1") (pinfunction "1_1") (pintype "passive"))
      (node (ref "C2") (pin "1") (pinfunction "1_1") (pintype "passive"))
      (node (ref "C20") (pin "1") (pinfunction "1_1") (pintype "passive"))
      (node (ref "C25") (pin "1") (pinfunction "1_1") (pintype "passive"))
      (node (ref "C26") (pin "2") (pinfunction "2_2") (pintype "passive"))
      (node (ref "C27") (pin "2") (pinfunction "2_2") (pintype "passive"))
      (node (ref "C29") (pin "2") (pinfunction "2_2") (pintype "passive"))
      (node (ref "C3") (pin "1") (pinfunction "1_1") (pintype "passive"))
      (node (ref "C33") (pin "A") (pinfunction "+_A") (pintype "passive"))
      (node (ref "C34") (pin "A") (pinfunction "+_A") (pintype "passive"))
      (node (ref "C35") (pin "1") (pinfunction "1_1") (pintype "passive"))
      (node (ref "C36") (pin "1") (pinfunction "1_1") (pintype "passive"))
      (node (ref "C38") (pin "1") (pinfunction "1_1") (pintype "passive"))
      (node (ref "C4") (pin "1") (pinfunction "1_1") (pintype "passive"))
      (node (ref "C5") (pin "1") (pinfunction "1_1") (pintype "passive"))
      (node (ref "C6") (pin "A") (pinfunction "+_A") (pintype "passive"))
      (node (ref "DA1") (pin "3") (pinfunction "OUT_3") (pintype "power_in"))
      (node (ref "DA6") (pin "8") (pinfunction "VDD_8") (pintype "bidirectional"))
      (node (ref "DD1") (pin "100") (pinfunction "VDD_100") (pintype "power_in"))
      (node (ref "DD1") (pin "11") (pinfunction "VDD_11") (pintype "power_in"))
      (node (ref "DD1") (pin "19") (pinfunction "VDD_19") (pintype "power_in"))
      (node (ref "DD1") (pin "28") (pinfunction "VDD_28") (pintype "power_in"))
      (node (ref "DD1") (pin "50") (pinfunction "VDD_50") (pintype "power_in"))
      (node (ref "DD1") (pin "75") (pinfunction "VDD_75") (pintype "power_in"))
      (node (ref "DD2") (pin "1") (pinfunction "VDDRTC_1") (pintype "power_in"))
      (node (ref "DD2") (pin "13") (pinfunction "VDD_13") (pintype "power_in"))
      (node (ref "DD2") (pin "14") (pinfunction "VDD_14") (pintype "power_in"))
      (node (ref "DD2") (pin "16") (pinfunction "VDD_16") (pintype "power_in"))
      (node (ref "DD3") (pin "13") (pinfunction "VDD_13") (pintype "bidirectional"))
      (node (ref "DD3") (pin "3") (pinfunction "VDD_3") (pintype "bidirectional"))
      (node (ref "DD3") (pin "8") (pinfunction "VLOGIC_8") (pintype "bidirectional"))
      (node (ref "DD5") (pin "1") (pinfunction "VDD_IO_1") (pintype "bidirectional"))
      (node (ref "DD5") (pin "14") (pinfunction "VDD_14") (pintype "bidirectional"))
      (node (ref "JP1") (pin "1") (pinfunction "1_1") (pintype "passive"))
      (node (ref "JP2") (pin "1") (pinfunction "1_1") (pintype "passive"))
      (node (ref "JP4") (pin "3") (pinfunction "3_3") (pintype "passive"))
      (node (ref "JP5") (pin "3") (pinfunction "3_3") (pintype "passive"))
      (node (ref "JP6") (pin "1") (pinfunction "1_1") (pintype "passive"))
      (node (ref "LED3") (pin "1") (pinfunction "BA_1") (pintype "bidirectional"))
      (node (ref "LED3") (pin "2") (pinfunction "RA_2") (pintype "bidirectional"))
      (node (ref "LED3") (pin "3") (pinfunction "GA_3") (pintype "bidirectional"))
      (node (ref "Q3") (pin "2") (pinfunction "S_2") (pintype "passive"))
      (node (ref "Q4") (pin "2") (pinfunction "S_2") (pintype "passive"))
      (node (ref "R1") (pin "2") (pinfunction "2_2") (pintype "passive"))
      (node (ref "R11") (pin "2") (pinfunction "2_2") (pintype "passive"))
      (node (ref "R15") (pin "1") (pinfunction "1_1") (pintype "passive"))
      (node (ref "R16") (pin "1") (pinfunction "1_1") (pintype "passive"))
      (node (ref "R17") (pin "2") (pinfunction "2_2") (pintype "passive"))
      (node (ref "R18") (pin "2") (pinfunction "2_2") (pintype "passive"))
      (node (ref "R19") (pin "2") (pinfunction "2_2") (pintype "passive"))
      (node (ref "R20") (pin "2") (pinfunction "2_2") (pintype "passive"))
      (node (ref "R21") (pin "2") (pinfunction "2_2") (pintype "passive"))
      (node (ref "R25") (pin "2") (pinfunction "2_2") (pintype "passive"))
      (node (ref "R27") (pin "2") (pinfunction "2_2") (pintype "passive"))
      (node (ref "R28") (pin "2") (pinfunction "2_2") (pintype "passive"))
      (node (ref "R7") (pin "2") (pinfunction "2_2") (pintype "passive"))
      (node (ref "U2") (pin "8") (pinfunction "VDD_8") (pintype "power_in"))
      (node (ref "U44") (pin "3") (pinfunction "VDDA_3") (pintype "power_in"))
      (node (ref "U44") (pin "4") (pinfunction "VDDD_4") (pintype "power_in"))
      (node (ref "U44") (pin "8") (pinfunction "XCLR_8") (pintype "input"))
      (node (ref "VD5") (pin "1") (pinfunction "A_1") (pintype "passive"))
      (node (ref "XP1") (pin "1") (pinfunction "1_1") (pintype "passive"))
      (node (ref "XP1") (pin "2") (pinfunction "2_2") (pintype "passive"))
      (node (ref "XP16") (pin "2") (pinfunction "2_2") (pintype "passive"))
      (node (ref "XP6") (pin "2") (pinfunction "2_2") (pintype "passive"))
    )
    (net (code "5") (name "5V_ENABLE") (class "Default")
      (node (ref "DD1") (pin "57") (pinfunction "PD10_57") (pintype "bidirectional"))
      (node (ref "R61") (pin "2") (pinfunction "2_2") (pintype "passive"))
    )
    (net (code "6") (name "5V_USB") (class "Default")
      (node (ref "D2") (pin "A") (pinfunction "A_A") (pintype "passive"))
      (node (ref "X1") (pin "VBUS") (pinfunction "VBUS_VBUS") (pintype "bidirectional"))
    )
    (net (code "7") (name "6V") (class "Default")
      (node (ref "C31") (pin "A") (pinfunction "+_A") (pintype "passive"))
      (node (ref "C42") (pin "1") (pinfunction "1_1") (pintype "passive"))
      (node (ref "D3") (pin "C") (pinfunction "C_C") (pintype "passive"))
      (node (ref "DA1") (pin "2") (pinfunction "IN_2") (pintype "power_in"))
      (node (ref "F1") (pin "2") (pinfunction "2_2") (pintype "passive"))
      (node (ref "F3") (pin "2") (pinfunction "2_2") (pintype "passive"))
      (node (ref "L1") (pin "1") (pinfunction "1_1") (pintype "passive"))
      (node (ref "R55") (pin "2") (pinfunction "2_2") (pintype "passive"))
      (node (ref "XP2") (pin "2") (pinfunction "2_2") (pintype "passive"))
    )
    (net (code "8") (name "ADIS_INT") (class "Default")
      (node (ref "DD1") (pin "98") (pinfunction "PE1_98") (pintype "bidirectional"))
      (node (ref "DD2") (pin "15") (pinfunction "DIO2_15") (pintype "bidirectional"))
    )
    (net (code "9") (name "ADIS_MISO") (class "Default")
      (node (ref "DD1") (pin "31") (pinfunction "PA6_31") (pintype "bidirectional"))
      (node (ref "DD2") (pin "22") (pinfunction "DOUT_22") (pintype "output"))
    )
    (net (code "10") (name "ADIS_MOSI") (class "Default")
      (node (ref "DD1") (pin "32") (pinfunction "PA7_32") (pintype "bidirectional"))
      (node (ref "DD2") (pin "19") (pinfunction "DIN_19") (pintype "input"))
    )
    (net (code "11") (name "ADIS_NRST") (class "Default")
      (node (ref "DD1") (pin "67") (pinfunction "PA8_67") (pintype "bidirectional"))
      (node (ref "DD2") (pin "18") (pinfunction "~{RST}_18") (pintype "input"))
      (node (ref "R8") (pin "1") (pinfunction "1_1") (pintype "passive"))
    )
    (net (code "12") (name "ADIS_NSS") (class "Default")
      (node (ref "DD1") (pin "29") (pinfunction "PA4_29") (pintype "bidirectional"))
      (node (ref "DD2") (pin "20") (pinfunction "~{CS}_20") (pintype "input"))
    )
    (net (code "13") (name "ADIS_SCK") (class "Default")
      (node (ref "DD1") (pin "30") (pinfunction "PA5_30") (pintype "bidirectional"))
      (node (ref "DD2") (pin "21") (pinfunction "SCLK_21") (pintype "input"))
    )
    (net (code "14") (name "AD_CLK") (class "Default")
      (node (ref "DA6") (pin "6") (pinfunction "CLK_6") (pintype "bidirectional"))
      (node (ref "DD1") (pin "26") (pinfunction "PA3_26") (pintype "bidirectional"))
    )
    (net (code "15") (name "AD_SDI") (class "Default")
      (node (ref "DA6") (pin "5") (pinfunction "SDI_5") (pintype "bidirectional"))
      (node (ref "DD1") (pin "82") (pinfunction "PD1_82") (pintype "bidirectional"))
    )
    (net (code "16") (name "BMP085_EOC") (class "Default")
      (node (ref "DD1") (pin "3") (pinfunction "PE4_3") (pintype "bidirectional"))
      (node (ref "R75") (pin "1") (pinfunction "1_1") (pintype "passive"))
    )
    (net (code "17") (name "BOOT_0") (class "Default")
      (node (ref "DD1") (pin "94") (pinfunction "BOOT_0_94") (pintype "input"))
      (node (ref "R3") (pin "2") (pinfunction "2_2") (pintype "passive"))
    )
    (net (code "18") (name "BOOT_1") (class "Default")
      (node (ref "DD1") (pin "37") (pinfunction "BOOT_1(PB2)_37") (pintype "bidirectional"))
      (node (ref "R2") (pin "2") (pinfunction "2_2") (pintype "passive"))
    )
    (net (code "19") (name "CURRENT_SENS") (class "Default")
      (node (ref "DD1") (pin "17") (pinfunction "PC2_17") (pintype "bidirectional"))
      (node (ref "IC2") (pin "1") (pinfunction "OUT_1") (pintype "output"))
    )
    (net (code "20") (name "EEPROM_PWR_EN") (class "Default")
      (node (ref "DD1") (pin "24") (pinfunction "PA1_24") (pintype "bidirectional"))
      (node (ref "Q4") (pin "1") (pinfunction "G_1") (pintype "passive"))
      (node (ref "R16") (pin "2") (pinfunction "2_2") (pintype "passive"))
    )
    (net (code "21") (name "FROM_GPS") (class "Default")
      (node (ref "DD1") (pin "69") (pinfunction "PA10_69") (pintype "bidirectional"))
      (node (ref "JP2") (pin "2") (pinfunction "2_2") (pintype "passive"))
    )
    (net (code "22") (name "FROM_XBEE") (class "Default")
      (node (ref "DD1") (pin "56") (pinfunction "PD9_56") (pintype "bidirectional"))
      (node (ref "JP1") (pin "2") (pinfunction "2_2") (pintype "passive"))
    )
    (net (code "23") (name "GND") (class "Default")
      (node (ref "BAT1") (pin "2") (pinfunction "-_2") (pintype "power_in"))
      (node (ref "C1") (pin "2") (pinfunction "2_2") (pintype "passive"))
      (node (ref "C10") (pin "2") (pinfunction "2_2") (pintype "passive"))
      (node (ref "C11") (pin "1") (pinfunction "1_1") (pintype "passive"))
      (node (ref "C12") (pin "1") (pinfunction "1_1") (pintype "passive"))
      (node (ref "C13") (pin "2") (pinfunction "2_2") (pintype "passive"))
      (node (ref "C19") (pin "1") (pinfunction "1_1") (pintype "passive"))
      (node (ref "C2") (pin "2") (pinfunction "2_2") (pintype "passive"))
      (node (ref "C20") (pin "2") (pinfunction "2_2") (pintype "passive"))
      (node (ref "C21") (pin "2") (pinfunction "2_2") (pintype "passive"))
      (node (ref "C23") (pin "1") (pinfunction "1_1") (pintype "passive"))
      (node (ref "C25") (pin "2") (pinfunction "2_2") (pintype "passive"))
      (node (ref "C26") (pin "1") (pinfunction "1_1") (pintype "passive"))
      (node (ref "C27") (pin "1") (pinfunction "1_1") (pintype "passive"))
      (node (ref "C28") (pin "1") (pinfunction "1_1") (pintype "passive"))
      (node (ref "C29") (pin "1") (pinfunction "1_1") (pintype "passive"))
      (node (ref "C3") (pin "2") (pinfunction "2_2") (pintype "passive"))
      (node (ref "C31") (pin "C") (pinfunction "-_C") (pintype "passive"))
      (node (ref "C32") (pin "2") (pinfunction "2_2") (pintype "passive"))
      (node (ref "C33") (pin "C") (pinfunction "-_C") (pintype "passive"))
      (node (ref "C34") (pin "C") (pinfunction "-_C") (pintype "passive"))
      (node (ref "C35") (pin "2") (pinfunction "2_2") (pintype "passive"))
      (node (ref "C36") (pin "2") (pinfunction "2_2") (pintype "passive"))
      (node (ref "C38") (pin "2") (pinfunction "2_2") (pintype "passive"))
      (node (ref "C4") (pin "2") (pinfunction "2_2") (pintype "passive"))
      (node (ref "C40") (pin "2") (pinfunction "2_2") (pintype "passive"))
      (node (ref "C42") (pin "2") (pinfunction "2_2") (pintype "passive"))
      (node (ref "C44") (pin "1") (pinfunction "1_1") (pintype "passive"))
      (node (ref "C5") (pin "2") (pinfunction "2_2") (pintype "passive"))
      (node (ref "C6") (pin "C") (pinfunction "-_C") (pintype "passive"))
      (node (ref "C7") (pin "C") (pinfunction "-_C") (pintype "passive"))
      (node (ref "C8") (pin "1") (pinfunction "1_1") (pintype "passive"))
      (node (ref "C9") (pin "2") (pinfunction "2_2") (pintype "passive"))
      (node (ref "D3") (pin "A") (pinfunction "A_A") (pintype "passive"))
      (node (ref "DA1") (pin "1") (pinfunction "ADJ_1") (pintype "input"))
      (node (ref "DA6") (pin "3") (pinfunction "GND_3") (pintype "bidirectional"))
      (node (ref "DD1") (pin "10") (pinfunction "GND_10") (pintype "power_in"))
      (node (ref "DD1") (pin "27") (pinfunction "GND_27") (pintype "power_in"))
      (node (ref "DD1") (pin "74") (pinfunction "GND_74") (pintype "power_in"))
      (node (ref "DD1") (pin "99") (pinfunction "GND_99") (pintype "power_in"))
      (node (ref "DD2") (pin "11") (pinfunction "GND_11") (pintype "power_in"))
      (node (ref "DD2") (pin "12") (pinfunction "GND_12") (pintype "power_in"))
      (node (ref "DD2") (pin "9") (pinfunction "GND_9") (pintype "power_in"))
      (node (ref "DD3") (pin "1") (pinfunction "CLKIN_1") (pintype "bidirectional"))
      (node (ref "DD3") (pin "11") (pinfunction "FSYNC_11") (pintype "bidirectional"))
      (node (ref "DD3") (pin "15") (pinfunction "GND_15") (pintype "bidirectional"))
      (node (ref "DD3") (pin "17") (pinfunction "GND_17") (pintype "bidirectional"))
      (node (ref "DD3") (pin "18") (pinfunction "GND_18") (pintype "bidirectional"))
      (node (ref "DD3") (pin "9") (pinfunction "AD0_9") (pintype "bidirectional"))
      (node (ref "DD4") (pin "10") (pinfunction "SHIELD_10") (pintype "power_in"))
      (node (ref "DD4") (pin "11") (pinfunction "SHIELD_11") (pintype "power_in"))
      (node (ref "DD4") (pin "12") (pinfunction "SHIELD_12") (pintype "power_in"))
      (node (ref "DD4") (pin "6") (pinfunction "GND_6") (pintype "power_in"))
      (node (ref "DD4") (pin "9") (pinfunction "SHIELD_9") (pintype "power_in"))
      (node (ref "DD5") (pin "10") (pinfunction "GND_10") (pintype "bidirectional"))
      (node (ref "DD5") (pin "11") (pinfunction "GND_11") (pintype "bidirectional"))
      (node (ref "DD5") (pin "7") (pinfunction "GND_7") (pintype "bidirectional"))
      (node (ref "IC1") (pin "1") (pinfunction "A0_1") (pintype "input"))
      (node (ref "IC1") (pin "2") (pinfunction "A1_2") (pintype "input"))
      (node (ref "IC1") (pin "3") (pinfunction "A2_3") (pintype "input"))
      (node (ref "IC1") (pin "4") (pinfunction "GND_4") (pintype "power_in"))
      (node (ref "IC1") (pin "7") (pinfunction "WP_7") (pintype "input"))
      (node (ref "JP1") (pin "10") (pinfunction "10_10") (pintype "passive"))
      (node (ref "JP2") (pin "10") (pinfunction "10_10") (pintype "passive"))
      (node (ref "JP4") (pin "1") (pinfunction "1_1") (pintype "passive"))
      (node (ref "JP5") (pin "1") (pinfunction "1_1") (pintype "passive"))
      (node (ref "JP6") (pin "2") (pinfunction "2_2") (pintype "passive"))
      (node (ref "LED1") (pin "C") (pinfunction "C_C") (pintype "passive"))
      (node (ref "LED2") (pin "C") (pinfunction "C_C") (pintype "passive"))
      (node (ref "R22") (pin "1") (pinfunction "1_1") (pintype "passive"))
      (node (ref "R23") (pin "1") (pinfunction "1_1") (pintype "passive"))
      (node (ref "R24") (pin "1") (pinfunction "1_1") (pintype "passive"))
      (node (ref "R32") (pin "2") (pinfunction "2_2") (pintype "passive"))
      (node (ref "R6") (pin "2") (pinfunction "2_2") (pintype "passive"))
      (node (ref "R64") (pin "2") (pinfunction "2_2") (pintype "passive"))
      (node (ref "R8") (pin "2") (pinfunction "2_2") (pintype "passive"))
      (node (ref "S2") (pin "P") (pinfunction "P_P") (pintype "passive"))
      (node (ref "U2") (pin "4") (pinfunction "GND_4") (pintype "power_in"))
      (node (ref "U2") (pin "5") (pinfunction "A2_5") (pintype "input"))
      (node (ref "U2") (pin "6") (pinfunction "A1_6") (pintype "input"))
      (node (ref "U2") (pin "7") (pinfunction "A0_7") (pintype "input"))
      (node (ref "U44") (pin "1") (pinfunction "GND_1") (pintype "power_in"))
      (node (ref "VD8") (pin "A") (pinfunction "A_A") (pintype "passive"))
      (node (ref "X1") (pin "GND") (pinfunction "GND_GND") (pintype "bidirectional"))
      (node (ref "XP1") (pin "10") (pinfunction "10_10") (pintype "passive"))
      (node (ref "XP1") (pin "12") (pinfunction "12_12") (pintype "passive"))
      (node (ref "XP1") (pin "14") (pinfunction "14_14") (pintype "passive"))
      (node (ref "XP1") (pin "16") (pinfunction "16_16") (pintype "passive"))
      (node (ref "XP1") (pin "18") (pinfunction "18_18") (pintype "passive"))
      (node (ref "XP1") (pin "20") (pinfunction "20_20") (pintype "passive"))
      (node (ref "XP1") (pin "4") (pinfunction "4_4") (pintype "passive"))
      (node (ref "XP1") (pin "6") (pinfunction "6_6") (pintype "passive"))
      (node (ref "XP1") (pin "8") (pinfunction "8_8") (pintype "passive"))
      (node (ref "XP16") (pin "3") (pinfunction "3_3") (pintype "passive"))
      (node (ref "XP2") (pin "3") (pinfunction "3_3") (pintype "passive"))
      (node (ref "XP6") (pin "3") (pinfunction "3_3") (pintype "passive"))
    )
    (net (code "24") (name "GND_A") (class "Default")
      (node (ref "C14") (pin "C") (pinfunction "-_C") (pintype "passive"))
      (node (ref "C15") (pin "2") (pinfunction "2_2") (pintype "passive"))
      (node (ref "C16") (pin "2") (pinfunction "2_2") (pintype "passive"))
      (node (ref "C17") (pin "2") (pinfunction "2_2") (pintype "passive"))
      (node (ref "C18") (pin "2") (pinfunction "2_2") (pintype "passive"))
      (node (ref "C22") (pin "2") (pinfunction "2_2") (pintype "passive"))
      (node (ref "C24") (pin "2") (pinfunction "2_2") (pintype "passive"))
      (node (ref "C37") (pin "1") (pinfunction "1_1") (pintype "passive"))
      (node (ref "C39") (pin "1") (pinfunction "1_1") (pintype "passive"))
      (node (ref "C41") (pin "2") (pinfunction "2_2") (pintype "passive"))
      (node (ref "C43") (pin "2") (pinfunction "2_2") (pintype "passive"))
      (node (ref "C46") (pin "2") (pinfunction "2_2") (pintype "passive"))
      (node (ref "C50") (pin "2") (pinfunction "2_2") (pintype "passive"))
      (node (ref "C52") (pin "C") (pinfunction "-_C") (pintype "passive"))
      (node (ref "C55") (pin "2") (pinfunction "2_2") (pintype "passive"))
      (node (ref "DA2") (pin "3") (pinfunction "GND_3") (pintype "power_in"))
      (node (ref "DA3") (pin "3") (pinfunction "GND_3") (pintype "power_in"))
      (node (ref "DA4") (pin "2") (pinfunction "GND_2") (pintype "input"))
      (node (ref "DA5") (pin "4") (pinfunction "-V_4") (pintype "power_in"))
      (node (ref "DA6") (pin "1") (pinfunction "B_1") (pintype "bidirectional"))
      (node (ref "DA6") (pin "2") (pinfunction "VSS_2") (pintype "bidirectional"))
      (node (ref "DD1") (pin "20") (pinfunction "VSS_A_20") (pintype "power_in"))
      (node (ref "IC2") (pin "2") (pinfunction "GND_2") (pintype "power_in"))
      (node (ref "IC3") (pin "2") (pinfunction "GND_2") (pintype "power_in"))
      (node (ref "R47") (pin "1") (pinfunction "1_1") (pintype "passive"))
      (node (ref "R56") (pin "1") (pinfunction "1_1") (pintype "passive"))
      (node (ref "R57") (pin "1") (pinfunction "1_1") (pintype "passive"))
      (node (ref "R6") (pin "1") (pinfunction "1_1") (pintype "passive"))
      (node (ref "T3") (pin "2") (pinfunction "E_2") (pintype "passive"))
      (node (ref "VD1") (pin "A") (pinfunction "A_A") (pintype "passive"))
      (node (ref "VD2") (pin "A") (pinfunction "A_A") (pintype "passive"))
      (node (ref "VD3") (pin "A") (pinfunction "A_A") (pintype "passive"))
    )
    (net (code "25") (name "GPS_ENABLE") (class "Default")
      (node (ref "DD1") (pin "97") (pinfunction "PE0_97") (pintype "bidirectional"))
      (node (ref "JP2") (pin "4") (pinfunction "4_4") (pintype "passive"))
    )
    (net (code "26") (name "GPS_PPS") (class "Default")
      (node (ref "DD1") (pin "23") (pinfunction "PA0_23") (pintype "bidirectional"))
      (node (ref "JP2") (pin "7") (pinfunction "7_7") (pintype "passive"))
    )
    (net (code "27") (name "I2C_FAST_SCL") (class "Default")
      (node (ref "DD1") (pin "47") (pinfunction "PB10_47") (pintype "bidirectional"))
      (node (ref "DD3") (pin "23") (pinfunction "SCL_23") (pintype "bidirectional"))
      (node (ref "DD5") (pin "2") (pinfunction "SCL_2") (pintype "bidirectional"))
      (node (ref "R28") (pin "1") (pinfunction "1_1") (pintype "passive"))
    )
    (net (code "28") (name "I2C_FAST_SDA") (class "Default")
      (node (ref "DD1") (pin "48") (pinfunction "PB11_48") (pintype "bidirectional"))
      (node (ref "DD3") (pin "24") (pinfunction "SDA_24") (pintype "bidirectional"))
      (node (ref "DD5") (pin "3") (pinfunction "SDA_3") (pintype "bidirectional"))
      (node (ref "R27") (pin "1") (pinfunction "1_1") (pintype "passive"))
    )
    (net (code "29") (name "I2C_SLOW_SCL") (class "Default")
      (node (ref "DD1") (pin "92") (pinfunction "PB6_92") (pintype "bidirectional"))
      (node (ref "IC1") (pin "6") (pinfunction "SCL_6") (pintype "open_collector"))
      (node (ref "JP6") (pin "5") (pinfunction "5_5") (pintype "passive"))
      (node (ref "R25") (pin "1") (pinfunction "1_1") (pintype "passive"))
      (node (ref "U2") (pin "2") (pinfunction "SCL_2") (pintype "open_collector"))
      (node (ref "U44") (pin "6") (pinfunction "SCL_6") (pintype "open_collector"))
    )
    (net (code "30") (name "I2C_SLOW_SDA") (class "Default")
      (node (ref "DD1") (pin "93") (pinfunction "PB7_93") (pintype "bidirectional"))
      (node (ref "IC1") (pin "5") (pinfunction "SDA_5") (pintype "open_collector"))
      (node (ref "JP6") (pin "6") (pinfunction "6_6") (pintype "passive"))
      (node (ref "R11") (pin "1") (pinfunction "1_1") (pintype "passive"))
      (node (ref "U2") (pin "1") (pinfunction "SDA_1") (pintype "open_collector"))
      (node (ref "U44") (pin "7") (pinfunction "SDA_7") (pintype "open_collector"))
    )
    (net (code "31") (name "LED_B") (class "Default")
      (node (ref "DD1") (pin "91") (pinfunction "PB5_91") (pintype "bidirectional"))
      (node (ref "R31") (pin "2") (pinfunction "2_2") (pintype "passive"))
    )
    (net (code "32") (name "LED_G") (class "Default")
      (node (ref "DD1") (pin "36") (pinfunction "PB1_36") (pintype "bidirectional"))
      (node (ref "R60") (pin "2") (pinfunction "2_2") (pintype "passive"))
    )
    (net (code "33") (name "LED_R") (class "Default")
      (node (ref "DD1") (pin "35") (pinfunction "PB0_35") (pintype "bidirectional"))
      (node (ref "R30") (pin "2") (pinfunction "2_2") (pintype "passive"))
    )
    (net (code "34") (name "MAG_INT") (class "Default")
      (node (ref "DD1") (pin "4") (pinfunction "PE5_4") (pintype "bidirectional"))
      (node (ref "DD5") (pin "9") (pinfunction "DRDY_9") (pintype "bidirectional"))
    )
    (net (code "35") (name "MAIN_SUPPLY") (class "Default")
      (node (ref "R51") (pin "1") (pinfunction "1_1") (pintype "passive"))
      (node (ref "R54") (pin "2") (pinfunction "2_2") (pintype "passive"))
      (node (ref "XP18") (pin "2") (pinfunction "2_2") (pintype "passive"))
    )
    (net (code "36") (name "MPU9150_INT") (class "Default")
      (node (ref "DD1") (pin "2") (pinfunction "PE3_2") (pintype "bidirectional"))
      (node (ref "R14") (pin "2") (pinfunction "2_2") (pintype "passive"))
    )
    (net (code "37") (name "MPXV_TEMP") (class "Default")
      (node (ref "C18") (pin "1") (pinfunction "1_1") (pintype "passive"))
      (node (ref "DD1") (pin "16") (pinfunction "PC1_16") (pintype "bidirectional"))
      (node (ref "R10") (pin "2") (pinfunction "2_2") (pintype "passive"))
      (node (ref "VD1") (pin "C") (pinfunction "C_C") (pintype "passive"))
    )
    (net (code "38") (name "Net-(BAT1-+)") (class "Default")
      (node (ref "BAT1") (pin "1") (pinfunction "+_1") (pintype "power_in"))
      (node (ref "VD4") (pin "1") (pinfunction "A_1") (pintype "passive"))
    )
    (net (code "39") (name "Net-(C7-+)") (class "Default")
      (node (ref "C7") (pin "A") (pinfunction "+_A") (pintype "passive"))
      (node (ref "C8") (pin "2") (pinfunction "2_2") (pintype "passive"))
      (node (ref "DD4") (pin "4") (pinfunction "VCC_4") (pintype "power_in"))
      (node (ref "Q3") (pin "3") (pinfunction "D_3") (pintype "passive"))
    )
    (net (code "40") (name "Net-(C14-+)") (class "Default")
      (node (ref "C14") (pin "A") (pinfunction "+_A") (pintype "passive"))
      (node (ref "C15") (pin "1") (pinfunction "1_1") (pintype "passive"))
      (node (ref "DA4") (pin "1") (pinfunction "IN_1") (pintype "power_in"))
      (node (ref "DA4") (pin "3") (pinfunction "EN_3") (pintype "input"))
      (node (ref "L1") (pin "2") (pinfunction "2_2") (pintype "passive"))
      (node (ref "Q1") (pin "2") (pinfunction "S_2") (pintype "passive"))
      (node (ref "R59") (pin "1") (pinfunction "1_1") (pintype "passive"))
    )
    (net (code "41") (name "Net-(D1-PadC)") (class "Default")
      (node (ref "D1") (pin "C") (pinfunction "C_C") (pintype "passive"))
      (node (ref "F3") (pin "1") (pinfunction "1_1") (pintype "passive"))
    )
    (net (code "42") (name "Net-(D2-PadC)") (class "Default")
      (node (ref "D2") (pin "C") (pinfunction "C_C") (pintype "passive"))
      (node (ref "F1") (pin "1") (pinfunction "1_1") (pintype "passive"))
    )
    (net (code "43") (name "Net-(DA2-OUT)") (class "Default")
      (node (ref "DA2") (pin "2") (pinfunction "OUT_2") (pintype "output"))
      (node (ref "R10") (pin "1") (pinfunction "1_1") (pintype "passive"))
    )
    (net (code "44") (name "Net-(DA3-OUT)") (class "Default")
      (node (ref "DA3") (pin "4") (pinfunction "OUT_4") (pintype "output"))
      (node (ref "R48") (pin "2") (pinfunction "2_2") (pintype "passive"))
    )
    (net (code "45") (name "Net-(DA4-BYPASS)") (class "Default")
      (node (ref "C16") (pin "1") (pinfunction "1_1") (pintype "passive"))
      (node (ref "DA4") (pin "4") (pinfunction "BYPASS_4") (pintype "input"))
    )
    (net (code "46") (name "Net-(DA5A-+IN)") (class "Default")
      (node (ref "C43") (pin "1") (pinfunction "1_1") (pintype "passive"))
      (node (ref "DA5") (pin "3") (pinfunction "+IN_3") (pintype "input"))
      (node (ref "R47") (pin "2") (pinfunction "2_2") (pintype "passive"))
      (node (ref "R48") (pin "1") (pinfunction "1_1") (pintype "passive"))
    )
    (net (code "47") (name "Net-(DA5A--IN)") (class "Default")
      (node (ref "DA5") (pin "2") (pinfunction "-IN_2") (pintype "input"))
      (node (ref "R33") (pin "1") (pinfunction "1_1") (pintype "passive"))
      (node (ref "R45") (pin "2") (pinfunction "2_2") (pintype "passive"))
    )
    (net (code "48") (name "Net-(DA6-W)") (class "Default")
      (node (ref "DA6") (pin "9") (pinfunction "W_9") (pintype "bidirectional"))
      (node (ref "R45") (pin "1") (pinfunction "1_1") (pintype "passive"))
    )
    (net (code "49") (name "Net-(DD1-OSC_IN)") (class "Default")
      (node (ref "C11") (pin "2") (pinfunction "2_2") (pintype "passive"))
      (node (ref "DD1") (pin "12") (pinfunction "OSC_IN_12") (pintype "input"))
      (node (ref "ZQ1") (pin "1") (pinfunction "P$1_1") (pintype "bidirectional"))
    )
    (net (code "50") (name "Net-(DD1-OSC_OUT)") (class "Default")
      (node (ref "C12") (pin "2") (pinfunction "2_2") (pintype "passive"))
      (node (ref "DD1") (pin "13") (pinfunction "OSC_OUT_13") (pintype "output"))
      (node (ref "ZQ1") (pin "3") (pinfunction "P$2_3") (pintype "bidirectional"))
    )
    (net (code "51") (name "Net-(DD1-PC3)") (class "Default")
      (node (ref "C37") (pin "2") (pinfunction "2_2") (pintype "passive"))
      (node (ref "DD1") (pin "18") (pinfunction "PC3_18") (pintype "bidirectional"))
      (node (ref "R54") (pin "1") (pinfunction "1_1") (pintype "passive"))
      (node (ref "R56") (pin "2") (pinfunction "2_2") (pintype "passive"))
      (node (ref "VD2") (pin "C") (pinfunction "C_C") (pintype "passive"))
    )
    (net (code "52") (name "Net-(DD1-PC4)") (class "Default")
      (node (ref "C39") (pin "2") (pinfunction "2_2") (pintype "passive"))
      (node (ref "DD1") (pin "33") (pinfunction "PC4_33") (pintype "bidirectional"))
      (node (ref "R55") (pin "1") (pinfunction "1_1") (pintype "passive"))
      (node (ref "R57") (pin "2") (pinfunction "2_2") (pintype "passive"))
      (node (ref "VD3") (pin "C") (pinfunction "C_C") (pintype "passive"))
    )
    (net (code "53") (name "Net-(DD1-PC13(TAMPER-RTC))") (class "Default")
      (node (ref "DD1") (pin "7") (pinfunction "PC13(TAMPER-RTC)_7") (pintype "bidirectional"))
      (node (ref "R32") (pin "1") (pinfunction "1_1") (pintype "passive"))
    )
    (net (code "54") (name "Net-(DD1-PC14(OSC32_IN))") (class "Default")
      (node (ref "C10") (pin "1") (pinfunction "1_1") (pintype "passive"))
      (node (ref "DD1") (pin "8") (pinfunction "PC14(OSC32_IN)_8") (pintype "bidirectional"))
      (node (ref "ZQ2") (pin "1") (pinfunction "P$1_1") (pintype "bidirectional"))
    )
    (net (code "55") (name "Net-(DD1-PC15(OSC32_OUT))") (class "Default")
      (node (ref "C9") (pin "1") (pinfunction "1_1") (pintype "passive"))
      (node (ref "DD1") (pin "9") (pinfunction "PC15(OSC32_OUT)_9") (pintype "bidirectional"))
      (node (ref "ZQ2") (pin "2") (pinfunction "P$2_2") (pintype "bidirectional"))
    )
    (net (code "56") (name "Net-(DD1-VCAP_1)") (class "Default")
      (node (ref "C44") (pin "2") (pinfunction "2_2") (pintype "passive"))
      (node (ref "DD1") (pin "49") (pinfunction "VCAP_1_49") (pintype "power_in"))
    )
    (net (code "57") (name "Net-(DD1-VCAP_2)") (class "Default")
      (node (ref "C23") (pin "2") (pinfunction "2_2") (pintype "passive"))
      (node (ref "DD1") (pin "73") (pinfunction "VCAP_2_73") (pintype "bidirectional"))
    )
    (net (code "58") (name "Net-(DD1-V_BAT)") (class "Default")
      (node (ref "C40") (pin "1") (pinfunction "1_1") (pintype "passive"))
      (node (ref "DD1") (pin "6") (pinfunction "V_BAT_6") (pintype "power_in"))
      (node (ref "VD4") (pin "3") (pinfunction "C_3") (pintype "passive"))
      (node (ref "VD5") (pin "3") (pinfunction "C_3") (pintype "passive"))
    )
    (net (code "59") (name "Net-(DD3-CPOUT)") (class "Default")
      (node (ref "C28") (pin "2") (pinfunction "2_2") (pintype "passive"))
      (node (ref "DD3") (pin "20") (pinfunction "CPOUT_20") (pintype "bidirectional"))
    )
    (net (code "60") (name "Net-(DD3-INT)") (class "Default")
      (node (ref "DD3") (pin "12") (pinfunction "INT_12") (pintype "bidirectional"))
      (node (ref "R14") (pin "1") (pinfunction "1_1") (pintype "passive"))
    )
    (net (code "61") (name "Net-(DD3-REGOUT)") (class "Default")
      (node (ref "C19") (pin "2") (pinfunction "2_2") (pintype "passive"))
      (node (ref "DD3") (pin "10") (pinfunction "REGOUT_10") (pintype "bidirectional"))
    )
    (net (code "62") (name "Net-(DD5-C1)") (class "Default")
      (node (ref "C32") (pin "1") (pinfunction "1_1") (pintype "passive"))
      (node (ref "DD5") (pin "6") (pinfunction "C1_6") (pintype "bidirectional"))
    )
    (net (code "63") (name "Net-(DD5-SETC)") (class "Default")
      (node (ref "C30") (pin "2") (pinfunction "2_2") (pintype "passive"))
      (node (ref "DD5") (pin "13") (pinfunction "SETC_13") (pintype "bidirectional"))
    )
    (net (code "64") (name "Net-(DD5-SETP)") (class "Default")
      (node (ref "C30") (pin "1") (pinfunction "1_1") (pintype "passive"))
      (node (ref "DD5") (pin "12") (pinfunction "SETP_12") (pintype "bidirectional"))
    )
    (net (code "65") (name "Net-(IC1-VCC)") (class "Default")
      (node (ref "C21") (pin "1") (pinfunction "1_1") (pintype "passive"))
      (node (ref "IC1") (pin "8") (pinfunction "VCC_8") (pintype "power_in"))
      (node (ref "Q4") (pin "3") (pinfunction "D_3") (pintype "passive"))
    )
    (net (code "66") (name "Net-(IC2-IN+)") (class "Default")
      (node (ref "C45") (pin "2") (pinfunction "2_2") (pintype "passive"))
      (node (ref "IC2") (pin "3") (pinfunction "IN+_3") (pintype "input"))
      (node (ref "R51") (pin "2") (pinfunction "2_2") (pintype "passive"))
    )
    (net (code "67") (name "Net-(IC2-IN-)") (class "Default")
      (node (ref "C45") (pin "1") (pinfunction "1_1") (pintype "passive"))
      (node (ref "IC2") (pin "4") (pinfunction "IN-_4") (pintype "input"))
      (node (ref "R36") (pin "2") (pinfunction "2_2") (pintype "passive"))
    )
    (net (code "68") (name "Net-(IC3-I)") (class "Default")
      (node (ref "C54") (pin "2") (pinfunction "2_2") (pintype "passive"))
      (node (ref "C55") (pin "1") (pinfunction "1_1") (pintype "passive"))
      (node (ref "IC3") (pin "3") (pinfunction "I_3") (pintype "input"))
      (node (ref "Q1") (pin "3") (pinfunction "D_3") (pintype "passive"))
    )
    (net (code "69") (name "Net-(JP4-Pad2)") (class "Default")
      (node (ref "JP4") (pin "2") (pinfunction "2_2") (pintype "passive"))
      (node (ref "R3") (pin "1") (pinfunction "1_1") (pintype "passive"))
      (node (ref "R5") (pin "1") (pinfunction "1_1") (pintype "passive"))
    )
    (net (code "70") (name "Net-(JP5-Pad2)") (class "Default")
      (node (ref "JP5") (pin "2") (pinfunction "2_2") (pintype "passive"))
      (node (ref "R2") (pin "1") (pinfunction "1_1") (pintype "passive"))
      (node (ref "R4") (pin "1") (pinfunction "1_1") (pintype "passive"))
    )
    (net (code "71") (name "Net-(LED1-PadA)") (class "Default")
      (node (ref "LED1") (pin "A") (pinfunction "A_A") (pintype "passive"))
      (node (ref "R5") (pin "2") (pinfunction "2_2") (pintype "passive"))
    )
    (net (code "72") (name "Net-(LED2-PadA)") (class "Default")
      (node (ref "LED2") (pin "A") (pinfunction "A_A") (pintype "passive"))
      (node (ref "R4") (pin "2") (pinfunction "2_2") (pintype "passive"))
    )
    (net (code "73") (name "Net-(LED3-BC)") (class "Default")
      (node (ref "LED3") (pin "6") (pinfunction "BC_6") (pintype "bidirectional"))
      (node (ref "R31") (pin "1") (pinfunction "1_1") (pintype "passive"))
    )
    (net (code "74") (name "Net-(LED3-GC)") (class "Default")
      (node (ref "LED3") (pin "4") (pinfunction "GC_4") (pintype "bidirectional"))
      (node (ref "R60") (pin "1") (pinfunction "1_1") (pintype "passive"))
    )
    (net (code "75") (name "Net-(LED3-RC)") (class "Default")
      (node (ref "LED3") (pin "5") (pinfunction "RC_5") (pintype "bidirectional"))
      (node (ref "R30") (pin "1") (pinfunction "1_1") (pintype "passive"))
    )
    (net (code "76") (name "Net-(Q1-G)") (class "Default")
      (node (ref "C54") (pin "1") (pinfunction "1_1") (pintype "passive"))
      (node (ref "Q1") (pin "1") (pinfunction "G_1") (pintype "passive"))
      (node (ref "R58") (pin "2") (pinfunction "2_2") (pintype "passive"))
    )
    (net (code "77") (name "Net-(R12-Pad1)") (class "Default")
      (node (ref "R12") (pin "1") (pinfunction "1_1") (pintype "passive"))
      (node (ref "X1") (pin "D-") (pinfunction "D-_D-") (pintype "bidirectional"))
    )
    (net (code "78") (name "Net-(R13-Pad1)") (class "Default")
      (node (ref "R13") (pin "1") (pinfunction "1_1") (pintype "passive"))
      (node (ref "X1") (pin "D+") (pinfunction "D+_D+") (pintype "bidirectional"))
    )
    (net (code "79") (name "Net-(R22-Pad2)") (class "Default")
      (node (ref "R22") (pin "2") (pinfunction "2_2") (pintype "passive"))
      (node (ref "XP1") (pin "19") (pinfunction "19_19") (pintype "passive"))
    )
    (net (code "80") (name "Net-(R23-Pad2)") (class "Default")
      (node (ref "R23") (pin "2") (pinfunction "2_2") (pintype "passive"))
      (node (ref "XP1") (pin "17") (pinfunction "17_17") (pintype "passive"))
    )
    (net (code "81") (name "Net-(R24-Pad2)") (class "Default")
      (node (ref "R24") (pin "2") (pinfunction "2_2") (pintype "passive"))
      (node (ref "XP1") (pin "11") (pinfunction "11_11") (pintype "passive"))
    )
    (net (code "82") (name "Net-(R29-Pad1)") (class "Default")
      (node (ref "R29") (pin "1") (pinfunction "1_1") (pintype "passive"))
      (node (ref "XP2") (pin "1") (pinfunction "1_1") (pintype "passive"))
    )
    (net (code "83") (name "Net-(R36-Pad1)") (class "Default")
      (node (ref "R36") (pin "1") (pinfunction "1_1") (pintype "passive"))
      (node (ref "XP18") (pin "1") (pinfunction "1_1") (pintype "passive"))
    )
    (net (code "84") (name "Net-(R38-Pad2)") (class "Default")
      (node (ref "R38") (pin "2") (pinfunction "2_2") (pintype "passive"))
      (node (ref "XP8") (pin "1") (pinfunction "1_1") (pintype "passive"))
    )
    (net (code "85") (name "Net-(R39-Pad2)") (class "Default")
      (node (ref "R39") (pin "2") (pinfunction "2_2") (pintype "passive"))
      (node (ref "XP9") (pin "1") (pinfunction "1_1") (pintype "passive"))
    )
    (net (code "86") (name "Net-(R40-Pad2)") (class "Default")
      (node (ref "R40") (pin "2") (pinfunction "2_2") (pintype "passive"))
      (node (ref "XP10") (pin "1") (pinfunction "1_1") (pintype "passive"))
    )
    (net (code "87") (name "Net-(R41-Pad2)") (class "Default")
      (node (ref "R41") (pin "2") (pinfunction "2_2") (pintype "passive"))
      (node (ref "XP11") (pin "1") (pinfunction "1_1") (pintype "passive"))
    )
    (net (code "88") (name "Net-(R42-Pad2)") (class "Default")
      (node (ref "R42") (pin "2") (pinfunction "2_2") (pintype "passive"))
      (node (ref "XP12") (pin "1") (pinfunction "1_1") (pintype "passive"))
    )
    (net (code "89") (name "Net-(R43-Pad2)") (class "Default")
      (node (ref "R43") (pin "2") (pinfunction "2_2") (pintype "passive"))
      (node (ref "XP13") (pin "1") (pinfunction "1_1") (pintype "passive"))
    )
    (net (code "90") (name "Net-(R44-Pad2)") (class "Default")
      (node (ref "R44") (pin "2") (pinfunction "2_2") (pintype "passive"))
      (node (ref "XP14") (pin "1") (pinfunction "1_1") (pintype "passive"))
    )
    (net (code "91") (name "Net-(R46-Pad2)") (class "Default")
      (node (ref "R46") (pin "2") (pinfunction "2_2") (pintype "passive"))
      (node (ref "XP15") (pin "1") (pinfunction "1_1") (pintype "passive"))
    )
    (net (code "92") (name "Net-(R64-Pad1)") (class "Default")
      (node (ref "R64") (pin "1") (pinfunction "1_1") (pintype "passive"))
      (node (ref "XP10") (pin "3") (pinfunction "3_3") (pintype "passive"))
      (node (ref "XP11") (pin "3") (pinfunction "3_3") (pintype "passive"))
      (node (ref "XP12") (pin "3") (pinfunction "3_3") (pintype "passive"))
      (node (ref "XP13") (pin "3") (pinfunction "3_3") (pintype "passive"))
      (node (ref "XP14") (pin "3") (pinfunction "3_3") (pintype "passive"))
      (node (ref "XP15") (pin "3") (pinfunction "3_3") (pintype "passive"))
      (node (ref "XP17") (pin "3") (pinfunction "3_3") (pintype "passive"))
      (node (ref "XP8") (pin "3") (pinfunction "3_3") (pintype "passive"))
      (node (ref "XP9") (pin "3") (pinfunction "3_3") (pintype "passive"))
    )
    (net (code "93") (name "Net-(T3-B)") (class "Default")
      (node (ref "R61") (pin "1") (pinfunction "1_1") (pintype "passive"))
      (node (ref "T3") (pin "1") (pinfunction "B_1") (pintype "passive"))
    )
    (net (code "94") (name "Net-(T3-C)") (class "Default")
      (node (ref "R58") (pin "1") (pinfunction "1_1") (pintype "passive"))
      (node (ref "R59") (pin "2") (pinfunction "2_2") (pintype "passive"))
      (node (ref "T3") (pin "3") (pinfunction "C_3") (pintype "passive"))
    )
    (net (code "95") (name "Net-(U44-EOC)") (class "Default")
      (node (ref "R75") (pin "2") (pinfunction "2_2") (pintype "passive"))
      (node (ref "U44") (pin "2") (pinfunction "EOC_2") (pintype "output"))
    )
    (net (code "96") (name "PRESS_DIFF") (class "Default")
      (node (ref "DA5") (pin "1") (pinfunction "OUT_1") (pintype "output"))
      (node (ref "DD1") (pin "15") (pinfunction "PC0_15") (pintype "bidirectional"))
      (node (ref "R33") (pin "2") (pinfunction "2_2") (pintype "passive"))
    )
    (net (code "97") (name "RECEIVER_PPM") (class "Default")
      (node (ref "DD1") (pin "96") (pinfunction "PB9_96") (pintype "bidirectional"))
      (node (ref "R29") (pin "2") (pinfunction "2_2") (pintype "passive"))
      (node (ref "VD8") (pin "C") (pinfunction "C_C") (pintype "passive"))
    )
    (net (code "98") (name "RESET") (class "Default")
      (node (ref "C13") (pin "1") (pinfunction "1_1") (pintype "passive"))
      (node (ref "DD1") (pin "14") (pinfunction "NRST_14") (pintype "bidirectional"))
      (node (ref "R7") (pin "1") (pinfunction "1_1") (pintype "passive"))
      (node (ref "S2") (pin "S") (pinfunction "S_S") (pintype "passive"))
      (node (ref "XP1") (pin "15") (pinfunction "15_15") (pintype "passive"))
    )
    (net (code "99") (name "SDC_PWR_EN") (class "Default")
      (node (ref "DD1") (pin "46") (pinfunction "PE15_46") (pintype "bidirectional"))
      (node (ref "Q3") (pin "1") (pinfunction "G_1") (pintype "passive"))
      (node (ref "R15") (pin "2") (pinfunction "2_2") (pintype "passive"))
    )
    (net (code "100") (name "SDIO_CK") (class "Default")
      (node (ref "DD1") (pin "80") (pinfunction "PC12_80") (pintype "bidirectional"))
      (node (ref "DD4") (pin "5") (pinfunction "SD_CK_5") (pintype "input"))
    )
    (net (code "101") (name "SDIO_CMD") (class "Default")
      (node (ref "DD1") (pin "83") (pinfunction "PD2_83") (pintype "bidirectional"))
      (node (ref "DD4") (pin "3") (pinfunction "SD_CMD_3") (pintype "bidirectional"))
    )
    (net (code "102") (name "SDIO_D0") (class "Default")
      (node (ref "DD1") (pin "65") (pinfunction "PC8_65") (pintype "bidirectional"))
      (node (ref "DD4") (pin "7") (pinfunction "SD_D0_7") (pintype "bidirectional"))
    )
    (net (code "103") (name "SDIO_D1") (class "Default")
      (node (ref "DD1") (pin "66") (pinfunction "PC9_66") (pintype "bidirectional"))
      (node (ref "DD4") (pin "8") (pinfunction "SD_D1_8") (pintype "bidirectional"))
    )
    (net (code "104") (name "SDIO_D2") (class "Default")
      (node (ref "DD1") (pin "78") (pinfunction "PC10_78") (pintype "bidirectional"))
      (node (ref "DD4") (pin "1") (pinfunction "SD_D2_1") (pintype "bidirectional"))
    )
    (net (code "105") (name "SDIO_D3") (class "Default")
      (node (ref "DD1") (pin "79") (pinfunction "PC11_79") (pintype "bidirectional"))
      (node (ref "DD4") (pin "2") (pinfunction "SD_D3_2") (pintype "bidirectional"))
    )
    (net (code "106") (name "SDIO_DETECT") (class "Default")
      (node (ref "DD1") (pin "43") (pinfunction "PE12_43") (pintype "bidirectional"))
      (node (ref "DD4") (pin "13") (pinfunction "DETECT_13") (pintype "output"))
      (node (ref "R1") (pin "1") (pinfunction "1_1") (pintype "passive"))
    )
    (net (code "107") (name "SONAR_PWM") (class "Default")
      (node (ref "DD1") (pin "25") (pinfunction "PA2_25") (pintype "bidirectional"))
      (node (ref "XP6") (pin "1") (pinfunction "1_1") (pintype "passive"))
    )
    (net (code "108") (name "SPI2_MISO_UEXT") (class "Default")
      (node (ref "DD1") (pin "53") (pinfunction "PB14_53") (pintype "bidirectional"))
      (node (ref "JP6") (pin "7") (pinfunction "7_7") (pintype "passive"))
    )
    (net (code "109") (name "SPI2_MOSI_UEXT") (class "Default")
      (node (ref "DD1") (pin "54") (pinfunction "PB15_54") (pintype "bidirectional"))
      (node (ref "JP6") (pin "8") (pinfunction "8_8") (pintype "passive"))
    )
    (net (code "110") (name "SPI2_NSS_UEXT") (class "Default")
      (node (ref "DD1") (pin "51") (pinfunction "PB12_51") (pintype "bidirectional"))
      (node (ref "JP6") (pin "10") (pinfunction "10_10") (pintype "passive"))
    )
    (net (code "111") (name "SPI2_SCK_UEXT") (class "Default")
      (node (ref "DD1") (pin "52") (pinfunction "PB13_52") (pintype "bidirectional"))
      (node (ref "JP6") (pin "9") (pinfunction "9_9") (pintype "passive"))
    )
    (net (code "112") (name "TACHOMETER") (class "Default")
      (node (ref "DD1") (pin "95") (pinfunction "PB8_95") (pintype "bidirectional"))
      (node (ref "XP16") (pin "1") (pinfunction "1_1") (pintype "passive"))
    )
    (net (code "113") (name "TCK") (class "Default")
      (node (ref "DD1") (pin "76") (pinfunction "JTCK(PA14)_76") (pintype "bidirectional"))
      (node (ref "R20") (pin "1") (pinfunction "1_1") (pintype "passive"))
      (node (ref "XP1") (pin "9") (pinfunction "9_9") (pintype "passive"))
    )
    (net (code "114") (name "TDI") (class "Default")
      (node (ref "DD1") (pin "77") (pinfunction "JTDI(PA15)_77") (pintype "bidirectional"))
      (node (ref "R18") (pin "1") (pinfunction "1_1") (pintype "passive"))
      (node (ref "XP1") (pin "5") (pinfunction "5_5") (pintype "passive"))
    )
    (net (code "115") (name "TDO") (class "Default")
      (node (ref "DD1") (pin "89") (pinfunction "JTDO(PB3)_89") (pintype "bidirectional"))
      (node (ref "R21") (pin "1") (pinfunction "1_1") (pintype "passive"))
      (node (ref "XP1") (pin "13") (pinfunction "13_13") (pintype "passive"))
    )
    (net (code "116") (name "TIM1_CH1") (class "Default")
      (node (ref "DD1") (pin "40") (pinfunction "PE9_40") (pintype "bidirectional"))
      (node (ref "R38") (pin "1") (pinfunction "1_1") (pintype "passive"))
    )
    (net (code "117") (name "TIM1_CH2") (class "Default")
      (node (ref "DD1") (pin "42") (pinfunction "PE11_42") (pintype "bidirectional"))
      (node (ref "R39") (pin "1") (pinfunction "1_1") (pintype "passive"))
    )
    (net (code "118") (name "TIM1_CH3") (class "Default")
      (node (ref "DD1") (pin "44") (pinfunction "PE13_44") (pintype "bidirectional"))
      (node (ref "R40") (pin "1") (pinfunction "1_1") (pintype "passive"))
    )
    (net (code "119") (name "TIM1_CH4") (class "Default")
      (node (ref "DD1") (pin "45") (pinfunction "PE14_45") (pintype "bidirectional"))
      (node (ref "R41") (pin "1") (pinfunction "1_1") (pintype "passive"))
    )
    (net (code "120") (name "TIM4_CH1") (class "Default")
      (node (ref "DD1") (pin "59") (pinfunction "PD12_59") (pintype "bidirectional"))
      (node (ref "R42") (pin "1") (pinfunction "1_1") (pintype "passive"))
    )
    (net (code "121") (name "TIM4_CH2") (class "Default")
      (node (ref "DD1") (pin "60") (pinfunction "PD13_60") (pintype "bidirectional"))
      (node (ref "R43") (pin "1") (pinfunction "1_1") (pintype "passive"))
    )
    (net (code "122") (name "TIM4_CH3") (class "Default")
      (node (ref "DD1") (pin "61") (pinfunction "PD14_61") (pintype "bidirectional"))
      (node (ref "R44") (pin "1") (pinfunction "1_1") (pintype "passive"))
    )
    (net (code "123") (name "TIM4_CH4") (class "Default")
      (node (ref "DD1") (pin "62") (pinfunction "PD15_62") (pintype "bidirectional"))
      (node (ref "R46") (pin "1") (pinfunction "1_1") (pintype "passive"))
    )
    (net (code "124") (name "TMS") (class "Default")
      (node (ref "DD1") (pin "72") (pinfunction "JTMS(PA13)_72") (pintype "bidirectional"))
      (node (ref "R19") (pin "1") (pinfunction "1_1") (pintype "passive"))
      (node (ref "XP1") (pin "7") (pinfunction "7_7") (pintype "passive"))
    )
    (net (code "125") (name "TO_GPS") (class "Default")
      (node (ref "DD1") (pin "68") (pinfunction "PA9_68") (pintype "bidirectional"))
      (node (ref "JP2") (pin "3") (pinfunction "3_3") (pintype "passive"))
    )
    (net (code "126") (name "TO_XBEE") (class "Default")
      (node (ref "DD1") (pin "55") (pinfunction "PD8_55") (pintype "bidirectional"))
      (node (ref "JP1") (pin "3") (pinfunction "3_3") (pintype "passive"))
    )
    (net (code "127") (name "TRST") (class "Default")
      (node (ref "DD1") (pin "90") (pinfunction "NJTRST(PB4)_90") (pintype "bidirectional"))
      (node (ref "R17") (pin "1") (pinfunction "1_1") (pintype "passive"))
      (node (ref "XP1") (pin "3") (pinfunction "3_3") (pintype "passive"))
    )
    (net (code "128") (name "USART6_RX_UEXT") (class "Default")
      (node (ref "DD1") (pin "64") (pinfunction "PC7_64") (pintype "bidirectional"))
      (node (ref "JP6") (pin "4") (pinfunction "4_4") (pintype "passive"))
    )
    (net (code "129") (name "USART6_TX_UEXT") (class "Default")
      (node (ref "DD1") (pin "63") (pinfunction "PC6_63") (pintype "bidirectional"))
      (node (ref "JP6") (pin "3") (pinfunction "3_3") (pintype "passive"))
    )
    (net (code "130") (name "USB_DM") (class "Default")
      (node (ref "DD1") (pin "70") (pinfunction "PA11_70") (pintype "bidirectional"))
      (node (ref "R12") (pin "2") (pinfunction "2_2") (pintype "passive"))
    )
    (net (code "131") (name "USB_DP") (class "Default")
      (node (ref "DD1") (pin "71") (pinfunction "PA12_71") (pintype "bidirectional"))
      (node (ref "R13") (pin "2") (pinfunction "2_2") (pintype "passive"))
    )
    (net (code "132") (name "V_IN") (class "Default")
      (node (ref "D1") (pin "A") (pinfunction "A_A") (pintype "passive"))
      (node (ref "XP10") (pin "2") (pinfunction "2_2") (pintype "passive"))
      (node (ref "XP11") (pin "2") (pinfunction "2_2") (pintype "passive"))
      (node (ref "XP12") (pin "2") (pinfunction "2_2") (pintype "passive"))
      (node (ref "XP13") (pin "2") (pinfunction "2_2") (pintype "passive"))
      (node (ref "XP14") (pin "2") (pinfunction "2_2") (pintype "passive"))
      (node (ref "XP15") (pin "2") (pinfunction "2_2") (pintype "passive"))
      (node (ref "XP17") (pin "2") (pinfunction "2_2") (pintype "passive"))
      (node (ref "XP8") (pin "2") (pinfunction "2_2") (pintype "passive"))
      (node (ref "XP9") (pin "2") (pinfunction "2_2") (pintype "passive"))
    )
    (net (code "133") (name "XBEE_CTS") (class "Default")
      (node (ref "DD1") (pin "58") (pinfunction "PD11_58") (pintype "bidirectional"))
      (node (ref "JP1") (pin "4") (pinfunction "4_4") (pintype "passive"))
    )
    (net (code "134") (name "XBEE_RESET") (class "Default")
      (node (ref "DD1") (pin "88") (pinfunction "PD7_88") (pintype "bidirectional"))
      (node (ref "JP1") (pin "5") (pinfunction "5_5") (pintype "passive"))
    )
    (net (code "135") (name "unconnected-(DD1-PC5-Pad34)") (class "Default")
      (node (ref "DD1") (pin "34") (pinfunction "PC5_34") (pintype "bidirectional"))
    )
    (net (code "136") (name "unconnected-(DD1-PD3-Pad84)") (class "Default")
      (node (ref "DD1") (pin "84") (pinfunction "PD3_84") (pintype "bidirectional"))
    )
    (net (code "137") (name "unconnected-(DD1-PD4-Pad85)") (class "Default")
      (node (ref "DD1") (pin "85") (pinfunction "PD4_85") (pintype "bidirectional"))
    )
    (net (code "138") (name "unconnected-(DD1-PD5-Pad86)") (class "Default")
      (node (ref "DD1") (pin "86") (pinfunction "PD5_86") (pintype "bidirectional"))
    )
    (net (code "139") (name "unconnected-(DD1-PD6-Pad87)") (class "Default")
      (node (ref "DD1") (pin "87") (pinfunction "PD6_87") (pintype "bidirectional"))
    )
    (net (code "140") (name "unconnected-(DD1-PE2-Pad1)") (class "Default")
      (node (ref "DD1") (pin "1") (pinfunction "PE2_1") (pintype "bidirectional"))
    )
    (net (code "141") (name "unconnected-(DD1-PE6-Pad5)") (class "Default")
      (node (ref "DD1") (pin "5") (pinfunction "PE6_5") (pintype "bidirectional"))
    )
    (net (code "142") (name "unconnected-(DD1-PE7-Pad38)") (class "Default")
      (node (ref "DD1") (pin "38") (pinfunction "PE7_38") (pintype "bidirectional"))
    )
    (net (code "143") (name "unconnected-(DD1-PE8-Pad39)") (class "Default")
      (node (ref "DD1") (pin "39") (pinfunction "PE8_39") (pintype "bidirectional"))
    )
    (net (code "144") (name "unconnected-(DD1-PE10-Pad41)") (class "Default")
      (node (ref "DD1") (pin "41") (pinfunction "PE10_41") (pintype "bidirectional"))
    )
    (net (code "145") (name "unconnected-(DD2-DIO1-Pad17)") (class "Default")
      (node (ref "DD2") (pin "17") (pinfunction "DIO1_17") (pintype "bidirectional"))
    )
    (net (code "146") (name "unconnected-(DD2-DIO3-Pad23)") (class "Default")
      (node (ref "DD2") (pin "23") (pinfunction "DIO3_23") (pintype "bidirectional"))
    )
    (net (code "147") (name "unconnected-(DD2-DIO4-Pad24)") (class "Default")
      (node (ref "DD2") (pin "24") (pinfunction "DIO4_24") (pintype "bidirectional"))
    )
    (net (code "148") (name "unconnected-(DD3-E_SCL-Pad7)") (class "Default")
      (node (ref "DD3") (pin "7") (pinfunction "E_SCL_7") (pintype "bidirectional"))
    )
    (net (code "149") (name "unconnected-(DD3-E_SDA-Pad6)") (class "Default")
      (node (ref "DD3") (pin "6") (pinfunction "E_SDA_6") (pintype "bidirectional"))
    )
    (net (code "150") (name "unconnected-(DD5-INT1-Pad5)") (class "Default")
      (node (ref "DD5") (pin "5") (pinfunction "INT1_5") (pintype "bidirectional"))
    )
    (net (code "151") (name "unconnected-(DD5-INT2-Pad4)") (class "Default")
      (node (ref "DD5") (pin "4") (pinfunction "INT2_4") (pintype "bidirectional"))
    )
    (net (code "152") (name "unconnected-(JP1-Pad6)") (class "Default")
      (node (ref "JP1") (pin "6") (pinfunction "6_6") (pintype "passive"))
    )
    (net (code "153") (name "unconnected-(JP1-Pad7)") (class "Default")
      (node (ref "JP1") (pin "7") (pinfunction "7_7") (pintype "passive"))
    )
    (net (code "154") (name "unconnected-(JP1-Pad8)") (class "Default")
      (node (ref "JP1") (pin "8") (pinfunction "8_8") (pintype "passive"))
    )
    (net (code "155") (name "unconnected-(JP1-Pad9)") (class "Default")
      (node (ref "JP1") (pin "9") (pinfunction "9_9") (pintype "passive"))
    )
    (net (code "156") (name "unconnected-(JP2-Pad5)") (class "Default")
      (node (ref "JP2") (pin "5") (pinfunction "5_5") (pintype "passive"))
    )
    (net (code "157") (name "unconnected-(JP2-Pad6)") (class "Default")
      (node (ref "JP2") (pin "6") (pinfunction "6_6") (pintype "passive"))
    )
    (net (code "158") (name "unconnected-(JP2-Pad8)") (class "Default")
      (node (ref "JP2") (pin "8") (pinfunction "8_8") (pintype "passive"))
    )
    (net (code "159") (name "unconnected-(JP2-Pad9)") (class "Default")
      (node (ref "JP2") (pin "9") (pinfunction "9_9") (pintype "passive"))
    )
    (net (code "160") (name "unconnected-(U2-ALERT-Pad3)") (class "Default")
      (node (ref "U2") (pin "3") (pinfunction "ALERT_3") (pintype "output"))
    )
    (net (code "161") (name "unconnected-(U44-NC-Pad5)") (class "Default")
      (node (ref "U44") (pin "5") (pinfunction "NC_5") (pintype "no_connect"))
    )
    (net (code "162") (name "unconnected-(XP17-Pad1)") (class "Default")
      (node (ref "XP17") (pin "1") (pinfunction "1_1") (pintype "passive"))
    )
  )
)
